# Flight-Mill-Battery.net
KiCad netlist of a schematic drawn in EAGLE
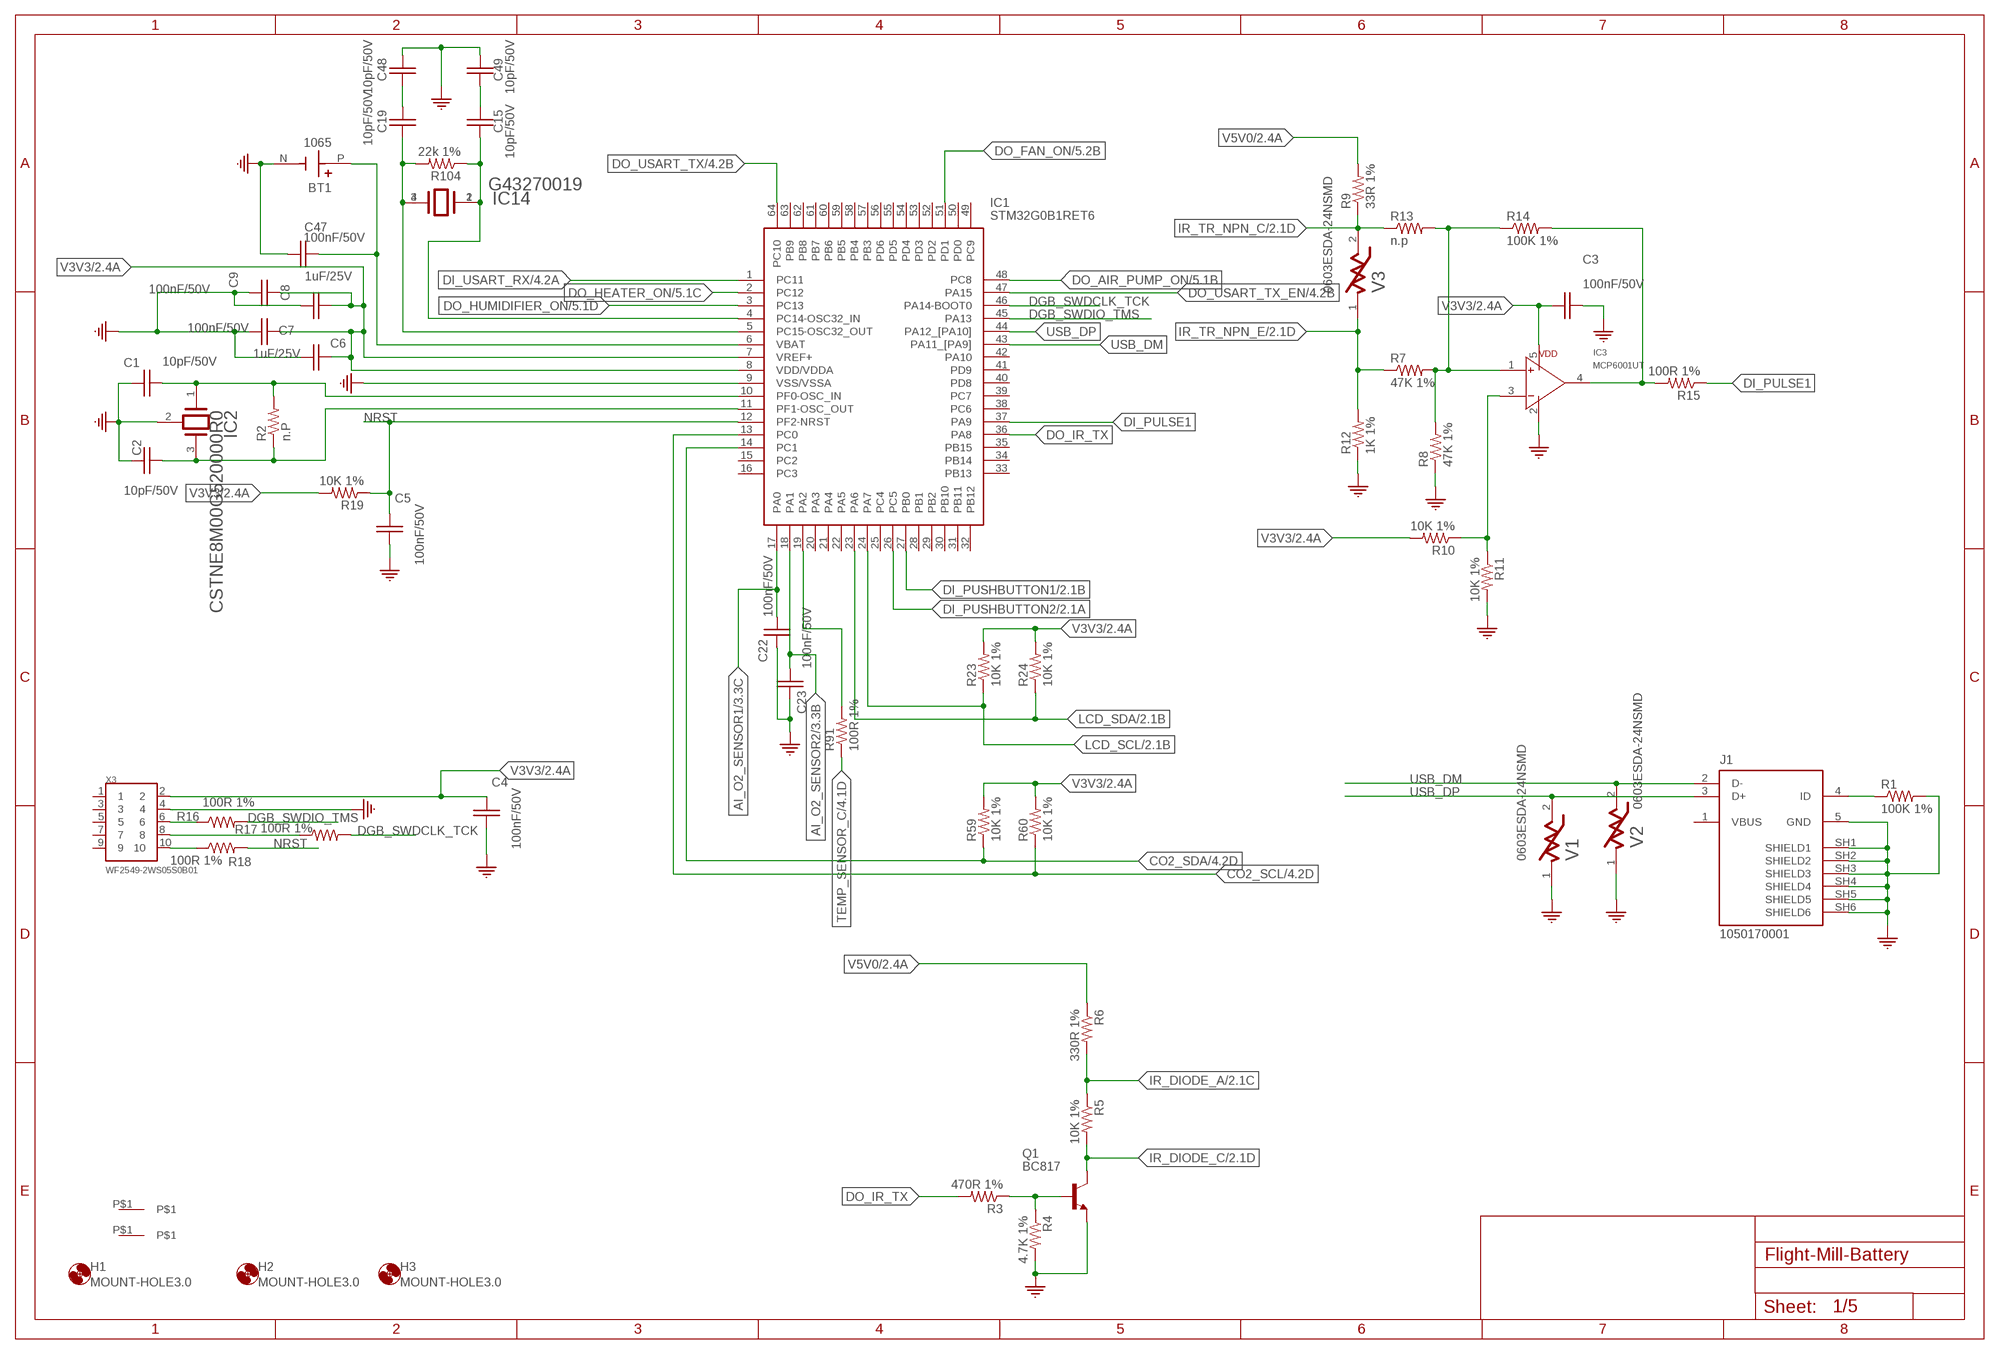
[diagram p0: schematic, sheet 1]
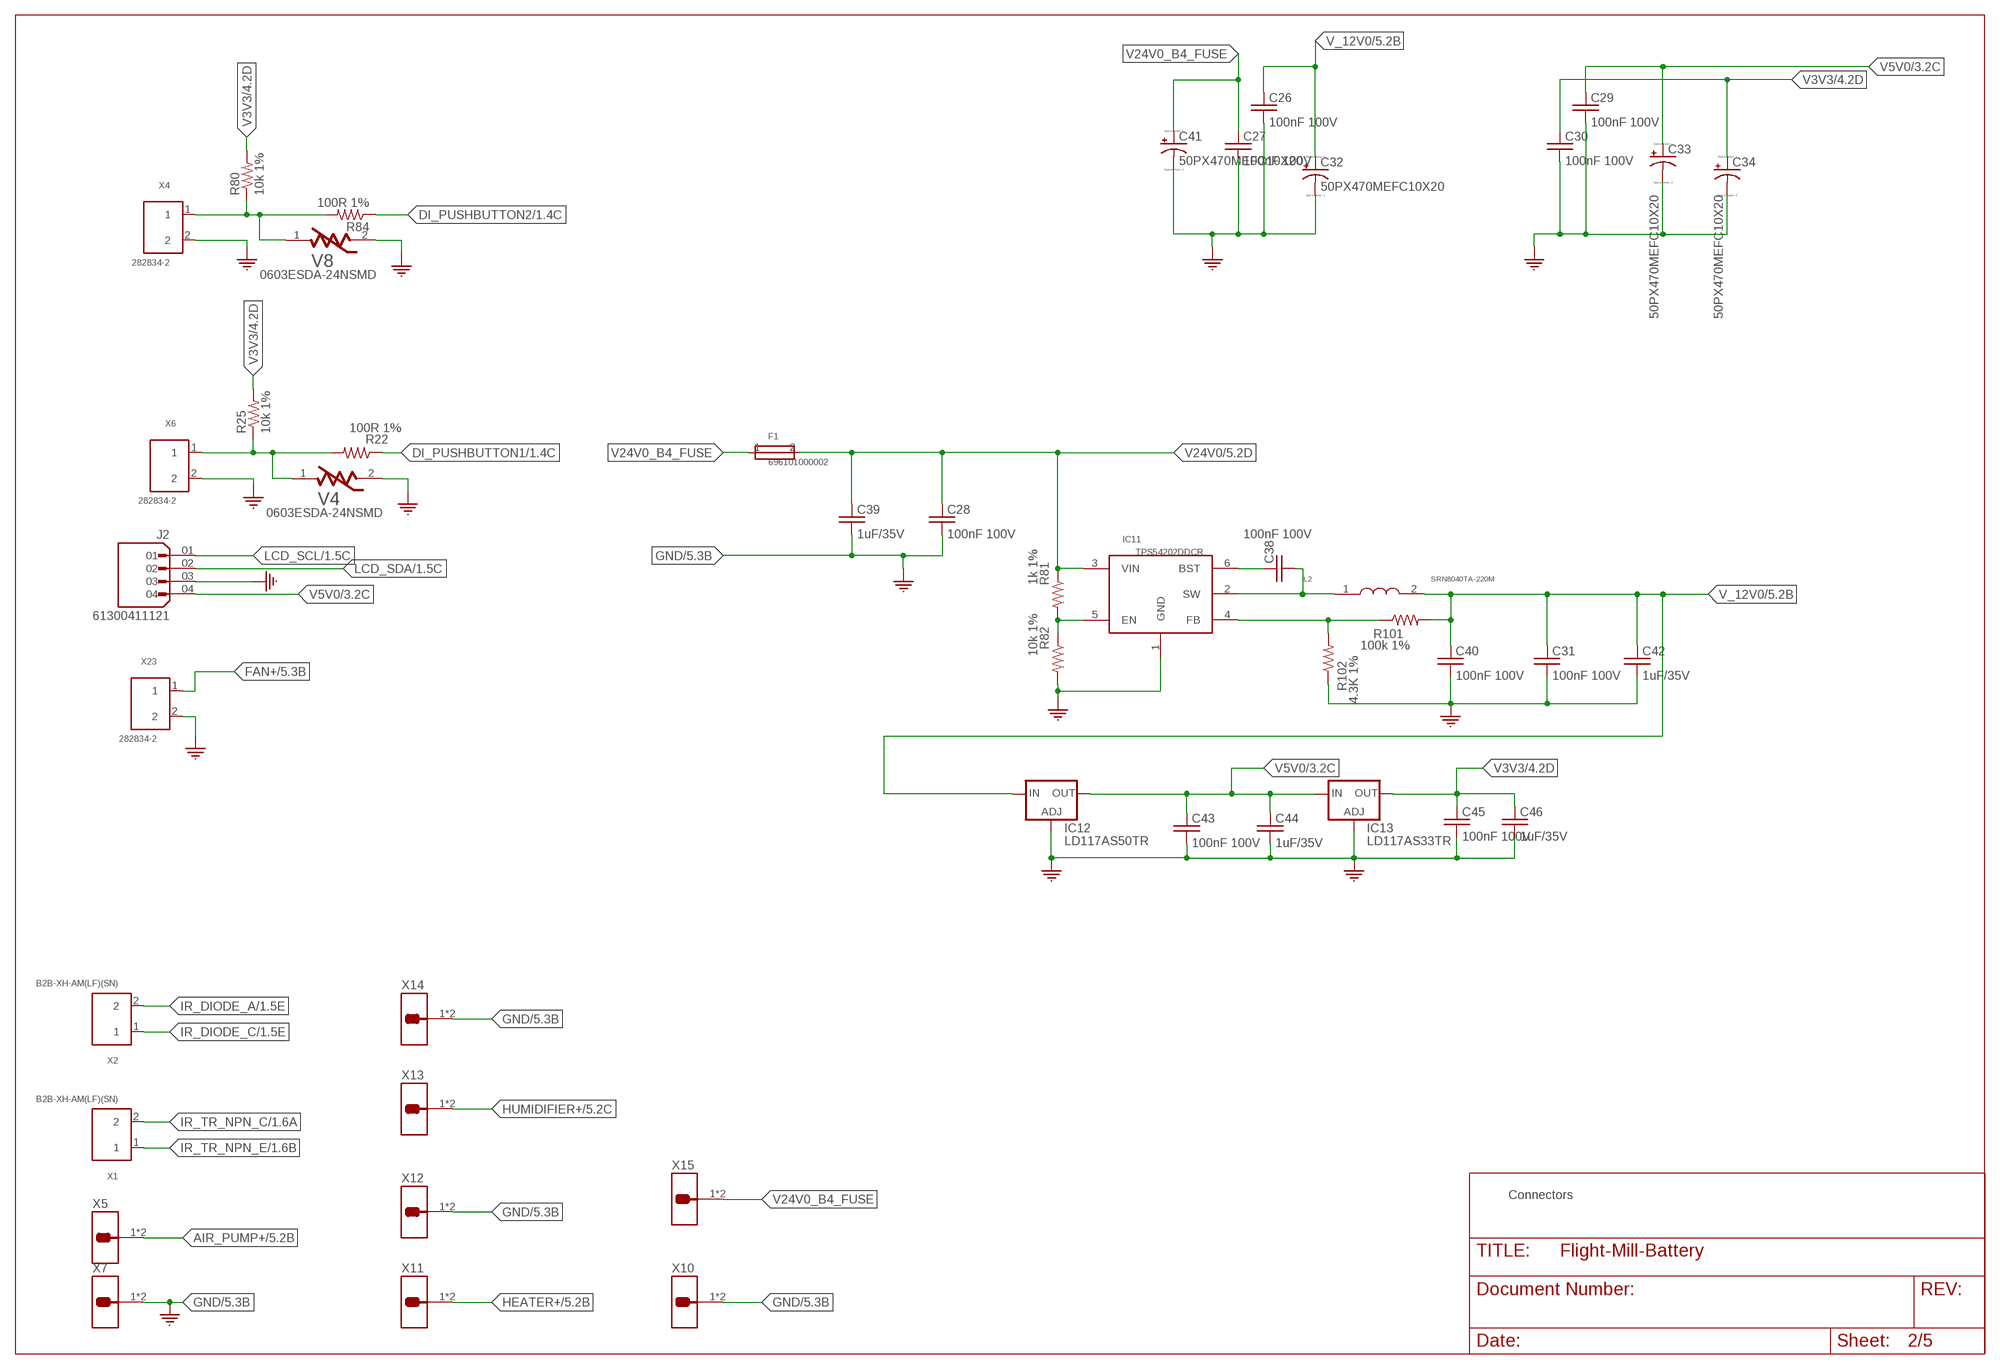
[diagram p1: schematic, sheet 2]
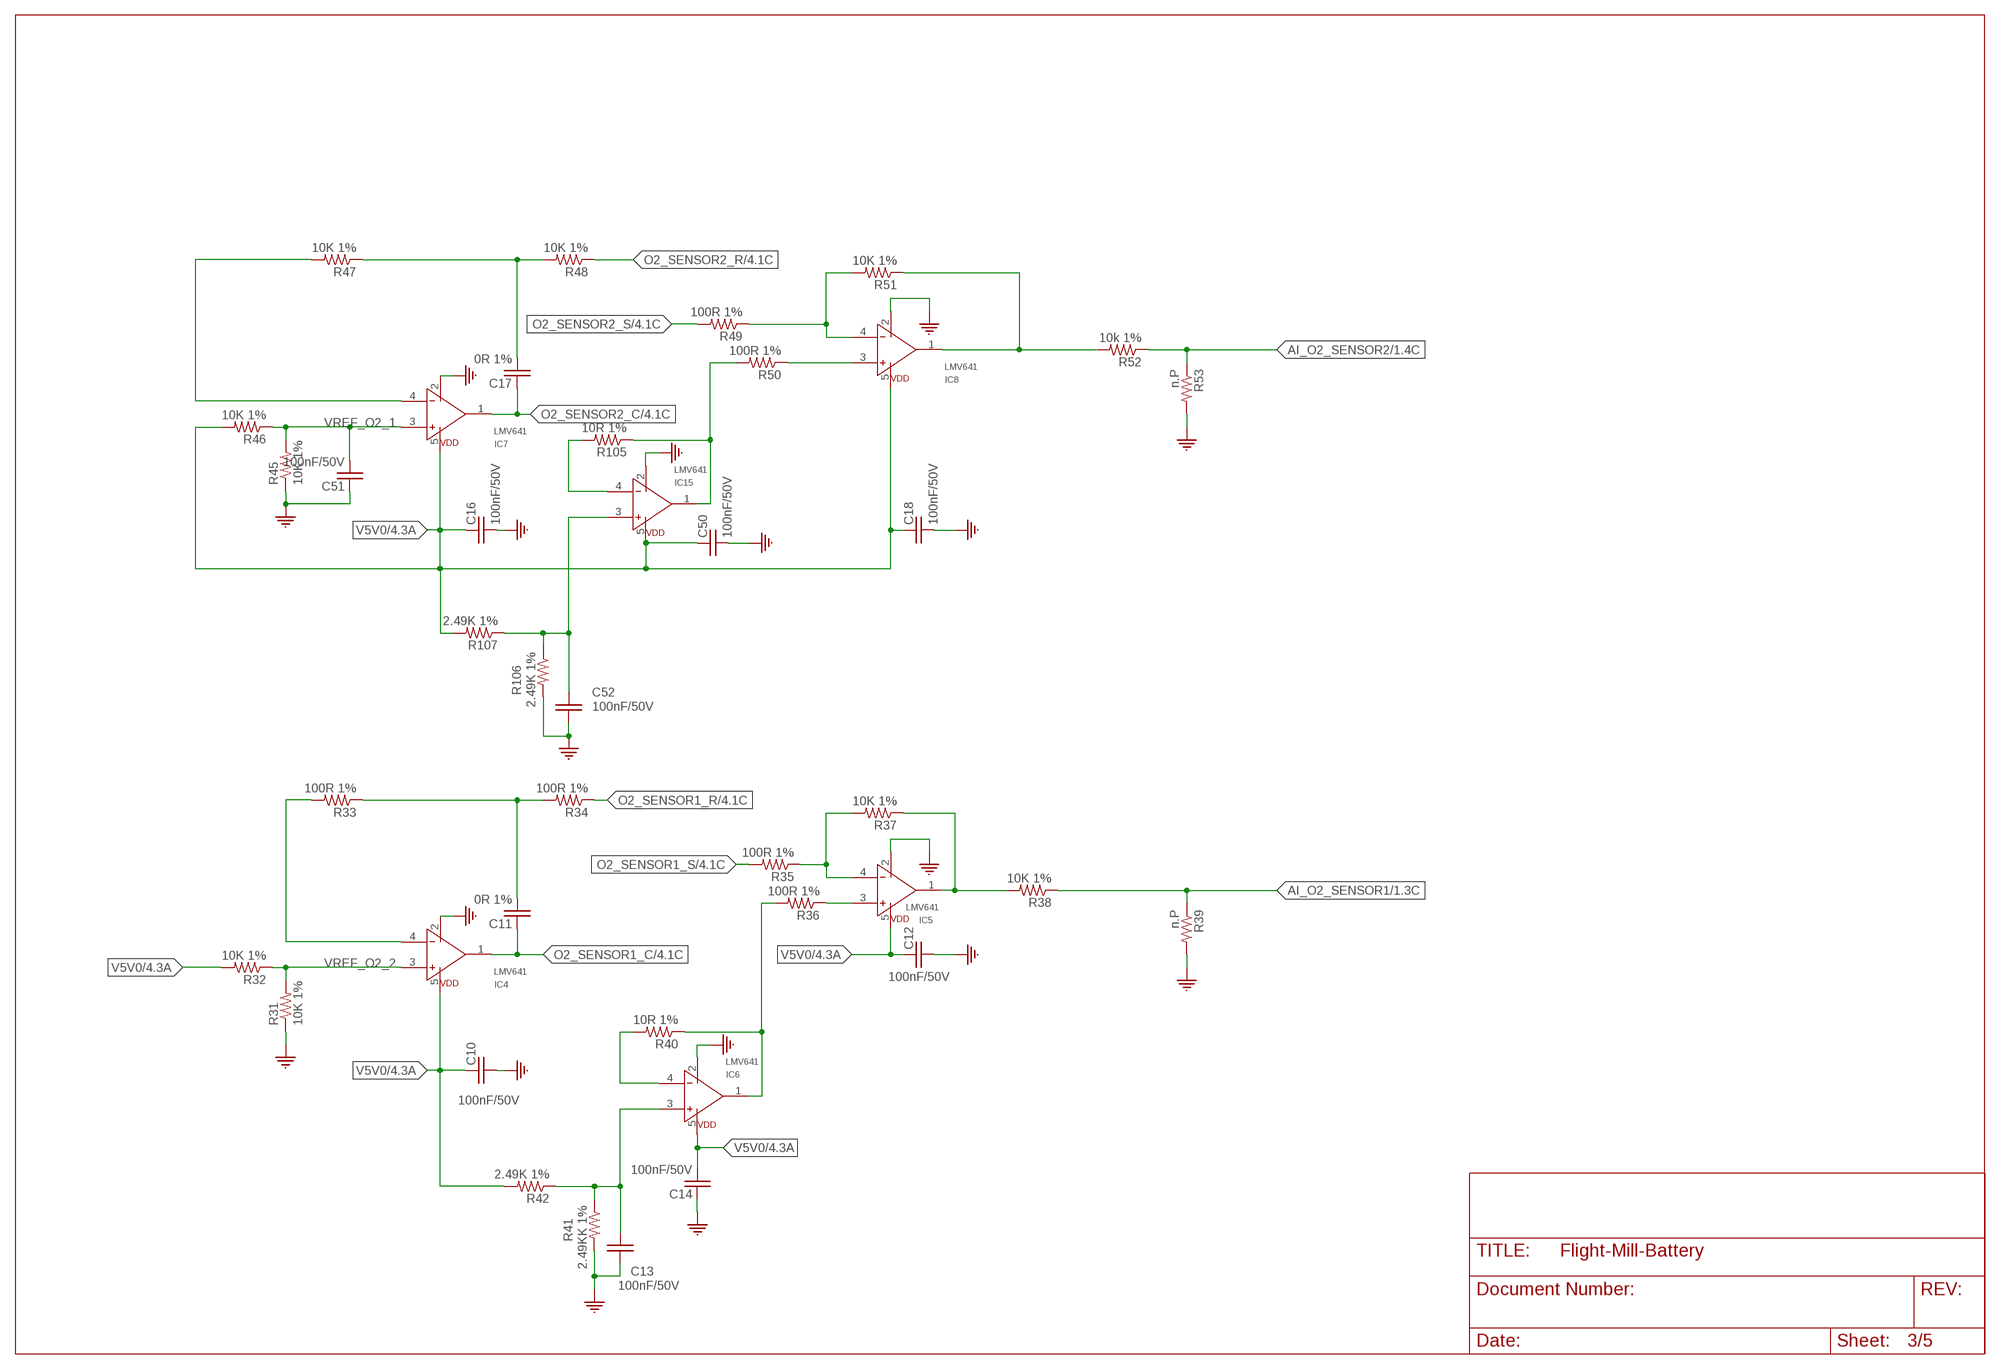
[diagram p2: schematic, sheet 3]
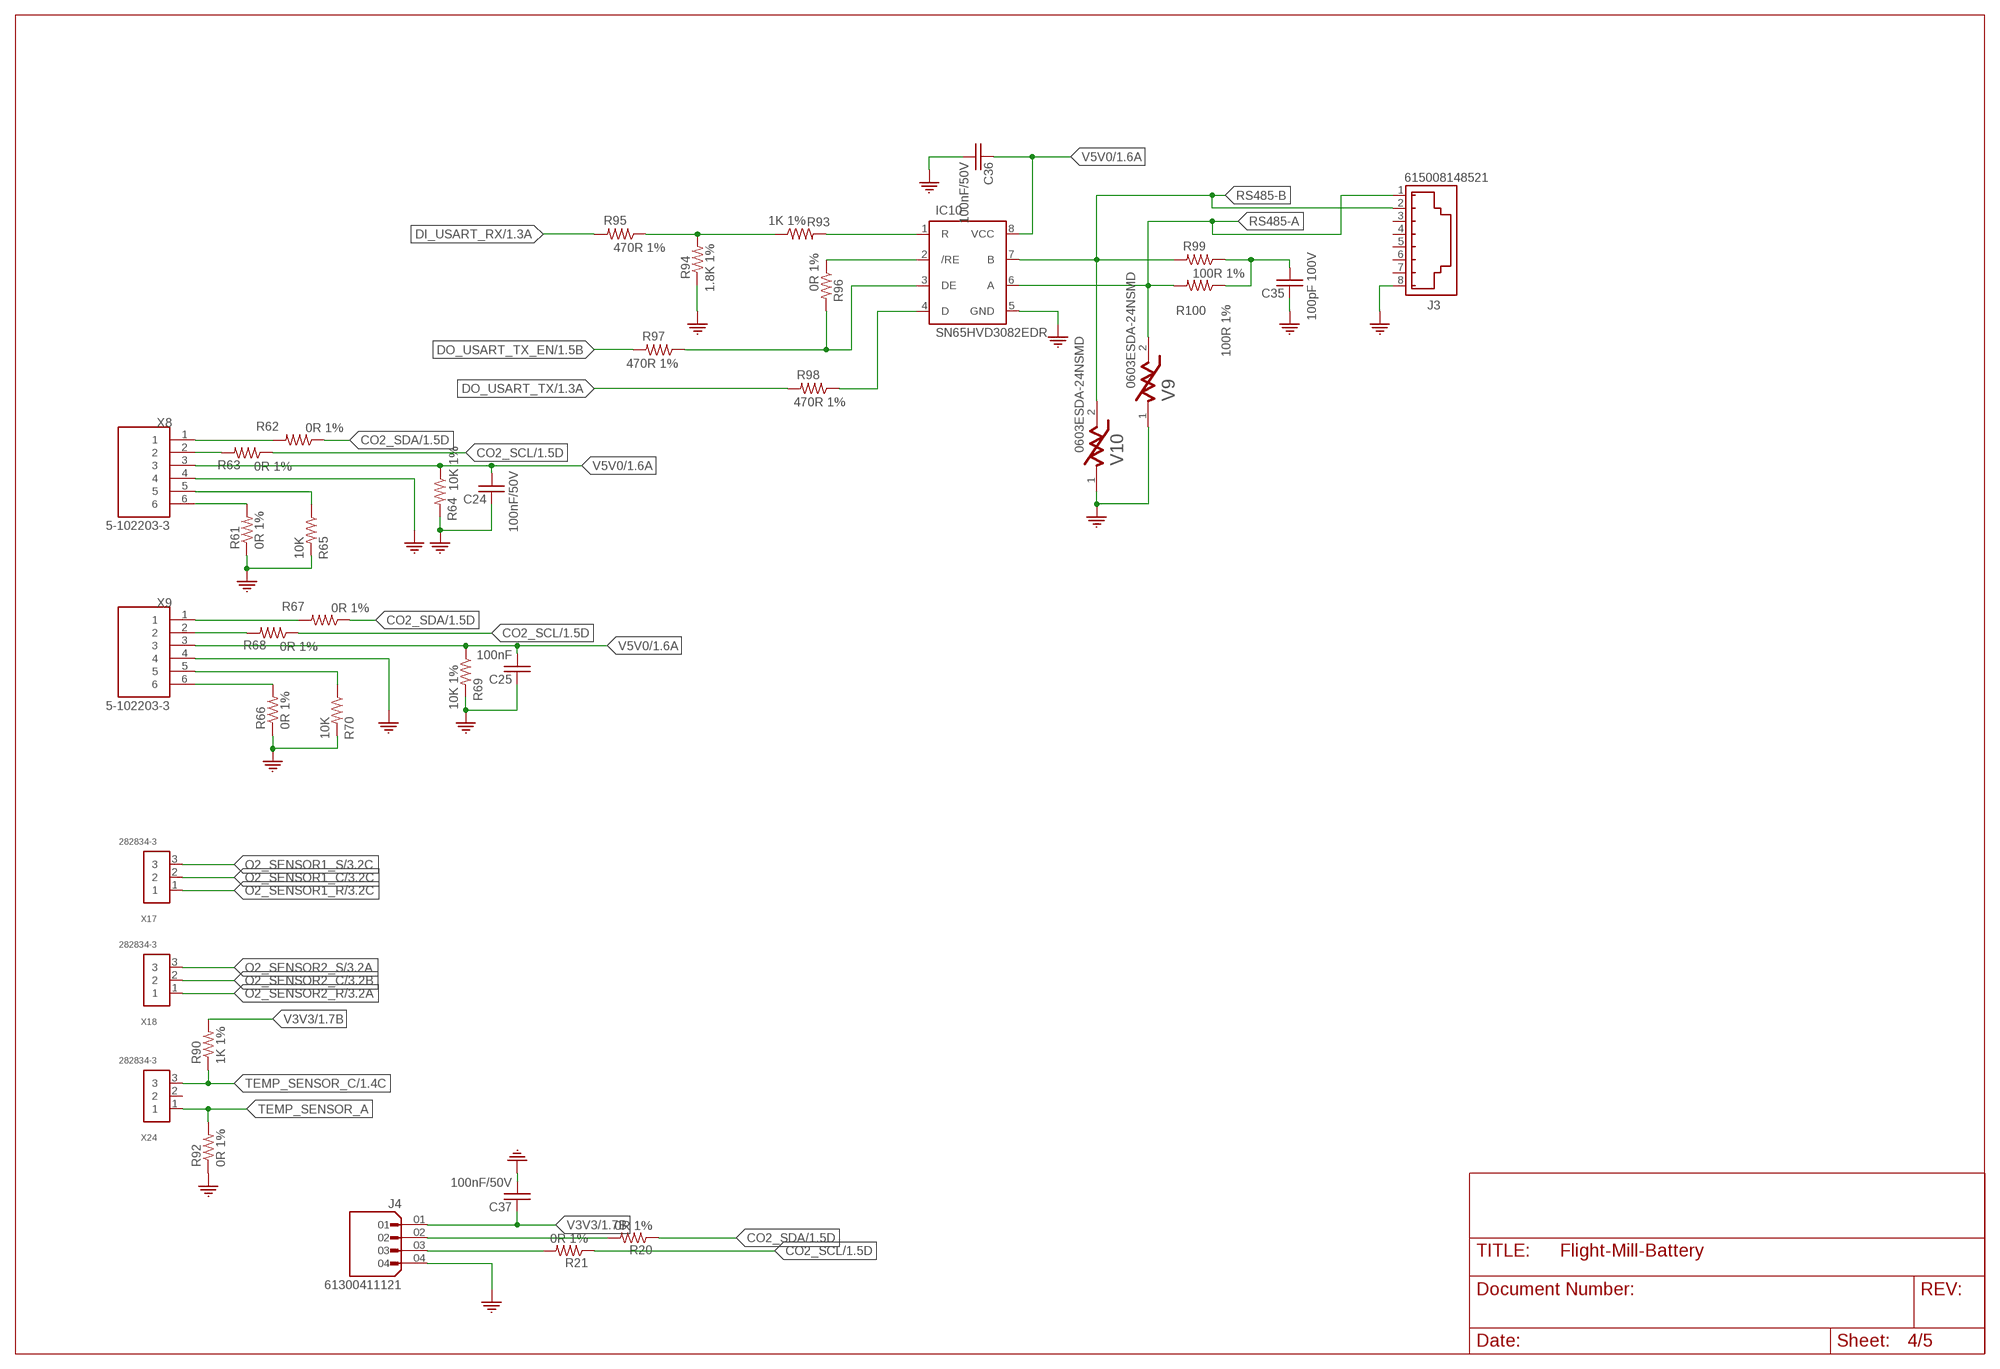
[diagram p3: schematic, sheet 4]
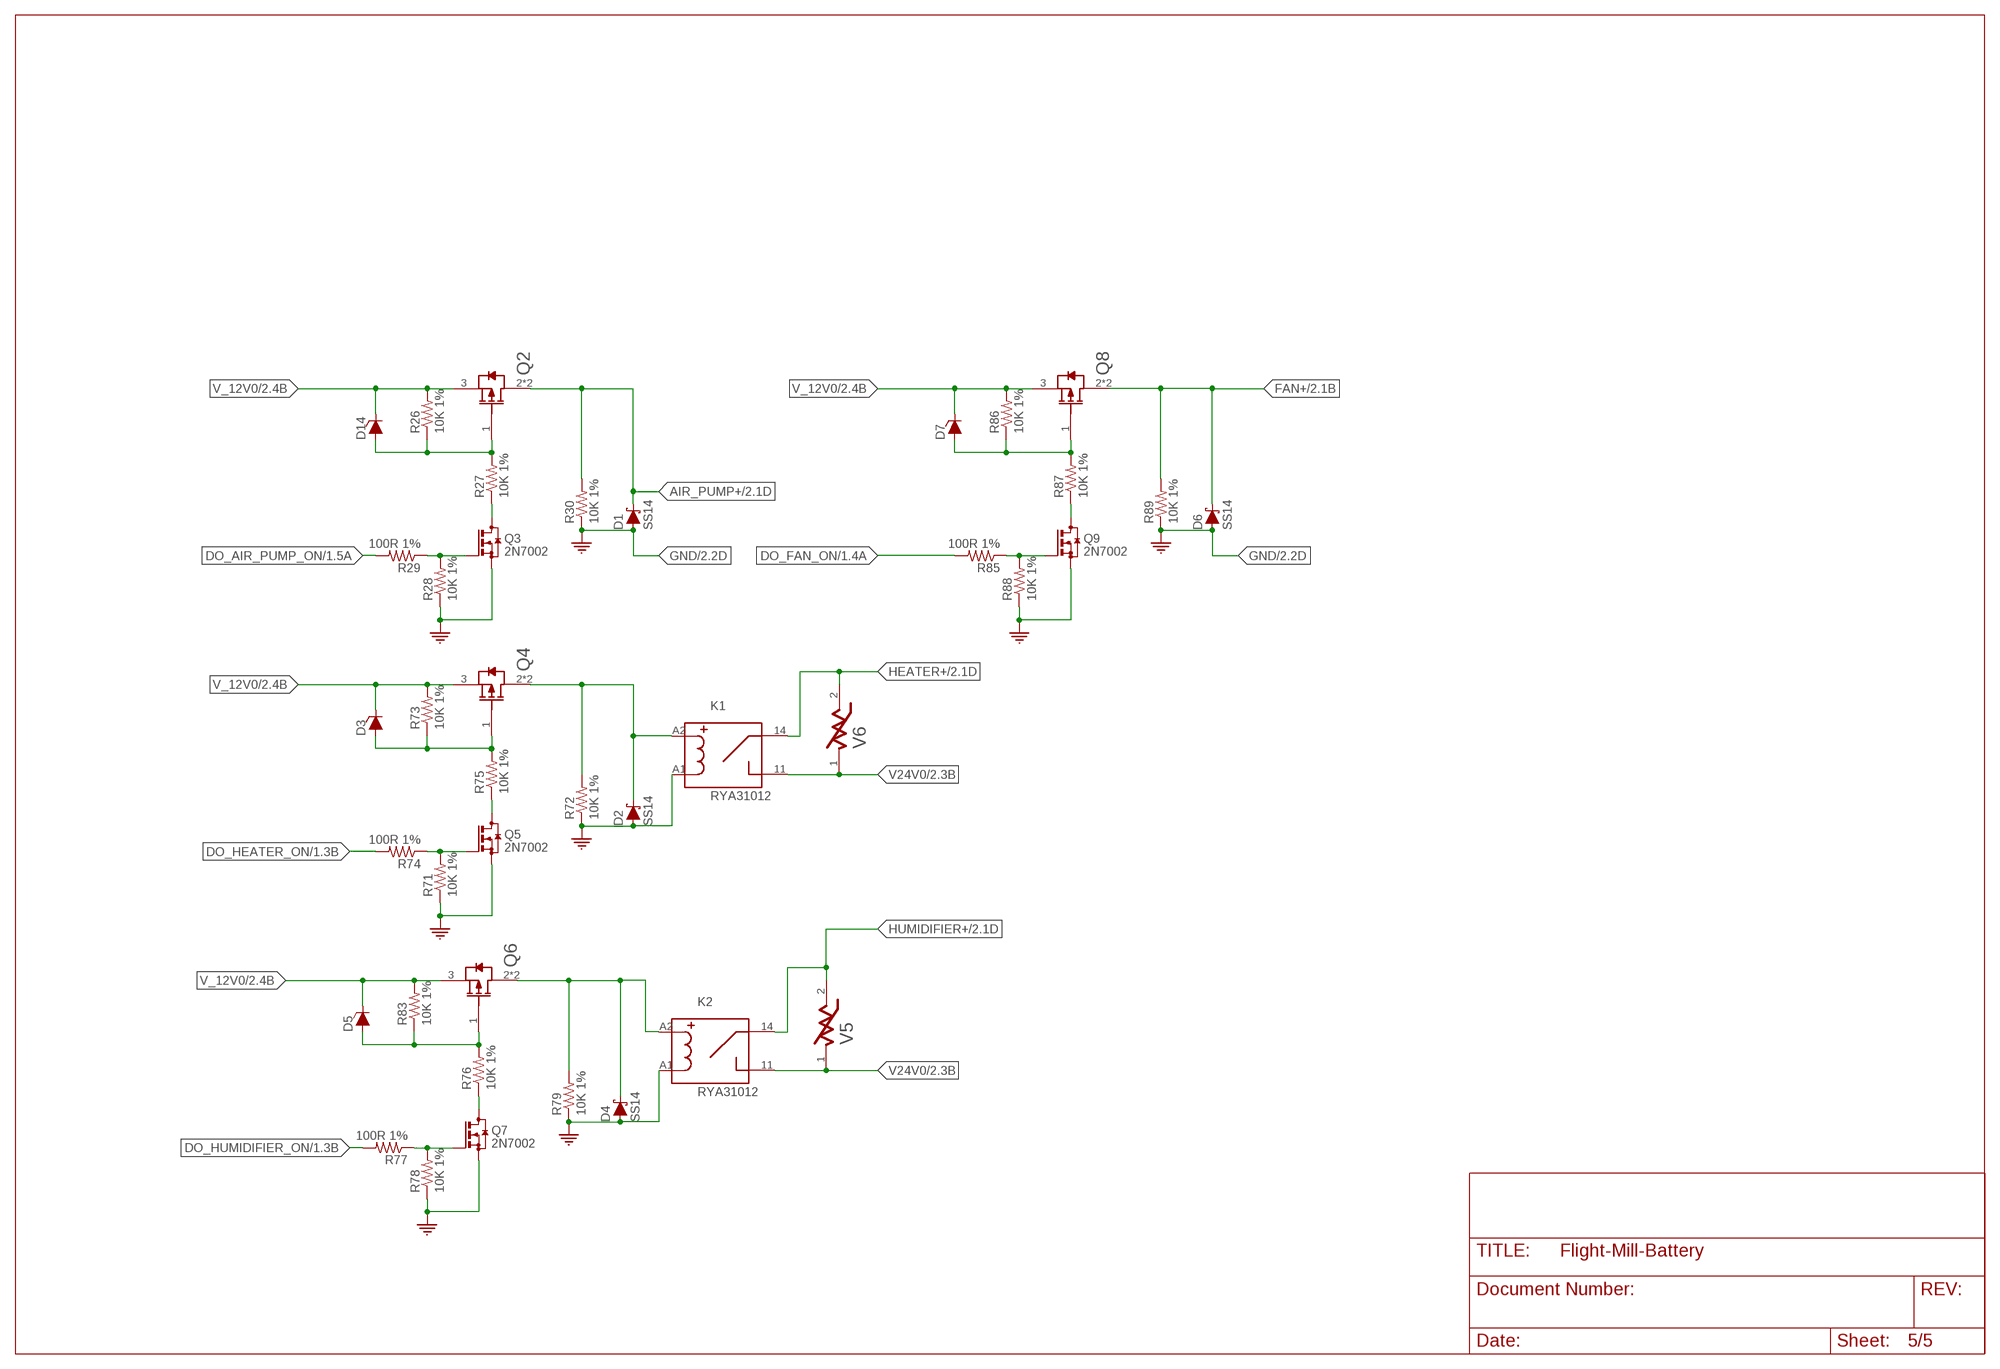
[diagram p4: schematic, sheet 5]

(export (version "E")
  (design (tool "Eeschema 10.0.6"))
  (components
    (comp (ref "C10")
      (value "100nF/50V")
      (footprint "eagle-import:EIA0603")
      (libsource (lib "eagle-import") (part "C_0603EIA0603"))
    )
    (comp (ref "C11")
      (value "0R 1%")
      (footprint "eagle-import:EIA0603")
      (libsource (lib "eagle-import") (part "C_0603EIA0603"))
    )
    (comp (ref "C12")
      (value "100nF/50V")
      (footprint "eagle-import:EIA0603")
      (libsource (lib "eagle-import") (part "C_0603EIA0603"))
    )
    (comp (ref "C13")
      (value "100nF/50V")
      (footprint "eagle-import:EIA0603")
      (libsource (lib "eagle-import") (part "C_0603EIA0603"))
    )
    (comp (ref "C14")
      (value "100nF/50V")
      (footprint "eagle-import:EIA0603")
      (libsource (lib "eagle-import") (part "C_0603EIA0603"))
    )
    (comp (ref "C16")
      (value "100nF/50V")
      (footprint "eagle-import:EIA0603")
      (libsource (lib "eagle-import") (part "C_0603EIA0603"))
    )
    (comp (ref "C17")
      (value "0R 1%")
      (footprint "eagle-import:EIA0603")
      (libsource (lib "eagle-import") (part "C_0603EIA0603"))
    )
    (comp (ref "C18")
      (value "100nF/50V")
      (footprint "eagle-import:EIA0603")
      (libsource (lib "eagle-import") (part "C_0603EIA0603"))
    )
    (comp (ref "C50")
      (value "100nF/50V")
      (footprint "eagle-import:EIA0603")
      (libsource (lib "eagle-import") (part "C_0603EIA0603"))
    )
    (comp (ref "C51")
      (value "100nF/50V")
      (footprint "eagle-import:EIA0603")
      (libsource (lib "eagle-import") (part "C_0603EIA0603"))
    )
    (comp (ref "C52")
      (value "100nF/50V")
      (footprint "eagle-import:EIA0603")
      (libsource (lib "eagle-import") (part "C_0603EIA0603"))
    )
    (comp (ref "IC4")
      (value "LMV641")
      (footprint "eagle-import:SOT-23-5")
      (fields (field (name "MFR") "Texas Instruments"))
      (libsource (lib "eagle-import") (part "LMV641"))
    )
    (comp (ref "IC5")
      (value "LMV641")
      (footprint "eagle-import:SOT-23-5")
      (fields (field (name "MFR") "Texas Instruments"))
      (libsource (lib "eagle-import") (part "LMV641"))
    )
    (comp (ref "IC6")
      (value "LMV641")
      (footprint "eagle-import:SOT-23-5")
      (fields (field (name "MFR") "Texas Instruments"))
      (libsource (lib "eagle-import") (part "LMV641"))
    )
    (comp (ref "IC7")
      (value "LMV641")
      (footprint "eagle-import:SOT-23-5")
      (fields (field (name "MFR") "Texas Instruments"))
      (libsource (lib "eagle-import") (part "LMV641"))
    )
    (comp (ref "IC8")
      (value "LMV641")
      (footprint "eagle-import:SOT-23-5")
      (fields (field (name "MFR") "Texas Instruments"))
      (libsource (lib "eagle-import") (part "LMV641"))
    )
    (comp (ref "IC15")
      (value "LMV641")
      (footprint "eagle-import:SOT-23-5")
      (fields (field (name "MFR") "Texas Instruments"))
      (libsource (lib "eagle-import") (part "LMV641"))
    )
    (comp (ref "R31")
      (value "10K 1%")
      (footprint "eagle-import:EIA0603")
      (libsource (lib "eagle-import") (part "R_0603"))
    )
    (comp (ref "R32")
      (value "10K 1%")
      (footprint "eagle-import:EIA0603")
      (libsource (lib "eagle-import") (part "R_0603"))
    )
    (comp (ref "R33")
      (value "100R 1%")
      (footprint "eagle-import:EIA0603")
      (libsource (lib "eagle-import") (part "R_0603"))
    )
    (comp (ref "R34")
      (value "100R 1%")
      (footprint "eagle-import:EIA0603")
      (libsource (lib "eagle-import") (part "R_0603"))
    )
    (comp (ref "R35")
      (value "100R 1%")
      (footprint "eagle-import:EIA0603")
      (libsource (lib "eagle-import") (part "R_0603"))
    )
    (comp (ref "R36")
      (value "100R 1%")
      (footprint "eagle-import:EIA0603")
      (libsource (lib "eagle-import") (part "R_0603"))
    )
    (comp (ref "R37")
      (value "10K 1%")
      (footprint "eagle-import:EIA0603")
      (libsource (lib "eagle-import") (part "R_0603"))
    )
    (comp (ref "R38")
      (value "10K 1%")
      (footprint "eagle-import:EIA0603")
      (libsource (lib "eagle-import") (part "R_0603"))
    )
    (comp (ref "R39")
      (value "n.P")
      (footprint "eagle-import:EIA0603")
      (libsource (lib "eagle-import") (part "R_0603"))
    )
    (comp (ref "R40")
      (value "10R 1%")
      (footprint "eagle-import:EIA0603")
      (libsource (lib "eagle-import") (part "R_0603"))
    )
    (comp (ref "R41")
      (value "2.49KK 1%")
      (footprint "eagle-import:EIA0603")
      (libsource (lib "eagle-import") (part "R_0603"))
    )
    (comp (ref "R42")
      (value "2.49K 1%")
      (footprint "eagle-import:EIA0603")
      (libsource (lib "eagle-import") (part "R_0603"))
    )
    (comp (ref "R45")
      (value "10K 1%")
      (footprint "eagle-import:EIA0603")
      (libsource (lib "eagle-import") (part "R_0603"))
    )
    (comp (ref "R46")
      (value "10K 1%")
      (footprint "eagle-import:EIA0603")
      (libsource (lib "eagle-import") (part "R_0603"))
    )
    (comp (ref "R47")
      (value "10K 1%")
      (footprint "eagle-import:EIA0603")
      (libsource (lib "eagle-import") (part "R_0603"))
    )
    (comp (ref "R48")
      (value "10K 1%")
      (footprint "eagle-import:EIA0603")
      (libsource (lib "eagle-import") (part "R_0603"))
    )
    (comp (ref "R49")
      (value "100R 1%")
      (footprint "eagle-import:EIA0603")
      (libsource (lib "eagle-import") (part "R_0603"))
    )
    (comp (ref "R50")
      (value "100R 1%")
      (footprint "eagle-import:EIA0603")
      (libsource (lib "eagle-import") (part "R_0603"))
    )
    (comp (ref "R51")
      (value "10K 1%")
      (footprint "eagle-import:EIA0603")
      (libsource (lib "eagle-import") (part "R_0603"))
    )
    (comp (ref "R52")
      (value "10k 1%")
      (footprint "eagle-import:EIA0603")
      (libsource (lib "eagle-import") (part "R_0603"))
    )
    (comp (ref "R53")
      (value "n.P")
      (footprint "eagle-import:EIA0603")
      (libsource (lib "eagle-import") (part "R_0603"))
    )
    (comp (ref "R105")
      (value "10R 1%")
      (footprint "eagle-import:EIA0603")
      (libsource (lib "eagle-import") (part "R_0603"))
    )
    (comp (ref "R106")
      (value "2.49K 1%")
      (footprint "eagle-import:EIA0603")
      (libsource (lib "eagle-import") (part "R_0603"))
    )
    (comp (ref "R107")
      (value "2.49K 1%")
      (footprint "eagle-import:EIA0603")
      (libsource (lib "eagle-import") (part "R_0603"))
    )
    (comp (ref "BT1")
      (value "1065")
      (footprint "eagle-import:BAT_1065")
      (fields (field (name "MF") "Keystone Electronics Corp."))
      (libsource (lib "eagle-import") (part "1065"))
    )
    (comp (ref "C1")
      (value "10pF/50V")
      (footprint "eagle-import:EIA0603")
      (libsource (lib "eagle-import") (part "C_0603EIA0603"))
    )
    (comp (ref "C2")
      (value "10pF/50V")
      (footprint "eagle-import:EIA0603")
      (libsource (lib "eagle-import") (part "C_0603EIA0603"))
    )
    (comp (ref "C3")
      (value "100nF/50V")
      (footprint "eagle-import:EIA0603")
      (libsource (lib "eagle-import") (part "C_0603EIA0603"))
    )
    (comp (ref "C4")
      (value "100nF/50V")
      (footprint "eagle-import:EIA0603")
      (libsource (lib "eagle-import") (part "C_0603EIA0603"))
    )
    (comp (ref "C5")
      (value "100nF/50V")
      (footprint "eagle-import:EIA0603")
      (libsource (lib "eagle-import") (part "C_0603EIA0603"))
    )
    (comp (ref "C6")
      (value "1uF/25V")
      (footprint "eagle-import:EIA0603")
      (libsource (lib "eagle-import") (part "C_0603EIA0603"))
    )
    (comp (ref "C7")
      (value "100nF/50V")
      (footprint "eagle-import:EIA0603")
      (libsource (lib "eagle-import") (part "C_0603EIA0603"))
    )
    (comp (ref "C8")
      (value "1uF/25V")
      (footprint "eagle-import:EIA0603")
      (libsource (lib "eagle-import") (part "C_0603EIA0603"))
    )
    (comp (ref "C9")
      (value "100nF/50V")
      (footprint "eagle-import:EIA0603")
      (libsource (lib "eagle-import") (part "C_0603EIA0603"))
    )
    (comp (ref "C15")
      (value "10pF/50V")
      (footprint "eagle-import:EIA0603")
      (libsource (lib "eagle-import") (part "C_0603EIA0603"))
    )
    (comp (ref "C19")
      (value "10pF/50V")
      (footprint "eagle-import:EIA0603")
      (libsource (lib "eagle-import") (part "C_0603EIA0603"))
    )
    (comp (ref "C22")
      (value "100nF/50V")
      (footprint "eagle-import:EIA0603")
      (libsource (lib "eagle-import") (part "C_0603EIA0603"))
    )
    (comp (ref "C23")
      (value "100nF/50V")
      (footprint "eagle-import:EIA0603")
      (libsource (lib "eagle-import") (part "C_0603EIA0603"))
    )
    (comp (ref "C47")
      (value "100nF/50V")
      (footprint "eagle-import:EIA0603")
      (libsource (lib "eagle-import") (part "C_0603EIA0603"))
    )
    (comp (ref "C48")
      (value "10pF/50V")
      (footprint "eagle-import:EIA0603")
      (libsource (lib "eagle-import") (part "C_0603EIA0603"))
    )
    (comp (ref "C49")
      (value "10pF/50V")
      (footprint "eagle-import:EIA0603")
      (libsource (lib "eagle-import") (part "C_0603EIA0603"))
    )
    (comp (ref "FID1")
      (value "FIDUCIAL")
      (footprint "eagle-import:FIDUCIAL")
      (libsource (lib "eagle-import") (part "FIDUCIAL"))
    )
    (comp (ref "FID2")
      (value "FIDUCIAL")
      (footprint "eagle-import:FIDUCIAL")
      (libsource (lib "eagle-import") (part "FIDUCIAL"))
    )
    (comp (ref "H1")
      (value "MOUNT-HOLE3.0")
      (footprint "eagle-import:3,0")
      (libsource (lib "eagle-import") (part "MOUNT-HOLE3.0"))
    )
    (comp (ref "H2")
      (value "MOUNT-HOLE3.0")
      (footprint "eagle-import:3,0")
      (libsource (lib "eagle-import") (part "MOUNT-HOLE3.0"))
    )
    (comp (ref "H3")
      (value "MOUNT-HOLE3.0")
      (footprint "eagle-import:3,0")
      (libsource (lib "eagle-import") (part "MOUNT-HOLE3.0"))
    )
    (comp (ref "IC1")
      (value "STM32G0B1RET6")
      (footprint "eagle-import:QFP50P1200X1200X160-64N")
      (fields (field (name "MOUSER_PART_NUMBER") "511-STM32G0B1RET6"))
      (libsource (lib "eagle-import") (part "STM32G0B1RET6"))
    )
    (comp (ref "IC2")
      (value "CSTNE8M00G520000R0")
      (footprint "eagle-import:CSTNE8M00G520000R0")
      (fields (field (name "MFR") "Murata"))
      (libsource (lib "eagle-import") (part "CSTNE8M00G520000R0"))
    )
    (comp (ref "IC3")
      (value "MCP6001UT")
      (footprint "eagle-import:SOT-23-5")
      (libsource (lib "eagle-import") (part "MCP6001UT"))
    )
    (comp (ref "IC14")
      (value "G43270019")
      (footprint "eagle-import:G43270019")
      (fields (field (name "MFR") "Diodes Inc"))
      (libsource (lib "eagle-import") (part "G43270019"))
    )
    (comp (ref "J1")
      (value "1050170001")
      (footprint "eagle-import:MOLEX_1050170001")
      (fields (field (name "MF") "Molex"))
      (libsource (lib "eagle-import") (part "1050170001"))
    )
    (comp (ref "Q1")
      (value "BC817")
      (footprint "eagle-import:SOT23")
      (fields (field (name "MFR") "NXP"))
      (libsource (lib "eagle-import") (part "BC817"))
    )
    (comp (ref "R1")
      (value "100K 1%")
      (footprint "eagle-import:EIA0603")
      (libsource (lib "eagle-import") (part "R_0603"))
    )
    (comp (ref "R2")
      (value "n.P")
      (footprint "eagle-import:EIA0603")
      (libsource (lib "eagle-import") (part "R_0603"))
    )
    (comp (ref "R3")
      (value "470R 1%")
      (footprint "eagle-import:EIA0603")
      (libsource (lib "eagle-import") (part "R_0603"))
    )
    (comp (ref "R4")
      (value "4.7K 1%")
      (footprint "eagle-import:EIA0603")
      (libsource (lib "eagle-import") (part "R_0603"))
    )
    (comp (ref "R5")
      (value "10K 1%")
      (footprint "eagle-import:EIA0603")
      (libsource (lib "eagle-import") (part "R_0603"))
    )
    (comp (ref "R6")
      (value "330R 1%")
      (footprint "eagle-import:EIA0603")
      (libsource (lib "eagle-import") (part "R_0603"))
    )
    (comp (ref "R7")
      (value "47K 1%")
      (footprint "eagle-import:EIA0603")
      (libsource (lib "eagle-import") (part "R_0603"))
    )
    (comp (ref "R8")
      (value "47K 1%")
      (footprint "eagle-import:EIA0603")
      (libsource (lib "eagle-import") (part "R_0603"))
    )
    (comp (ref "R9")
      (value "33R 1%")
      (footprint "eagle-import:EIA0603")
      (libsource (lib "eagle-import") (part "R_0603"))
    )
    (comp (ref "R10")
      (value "10K 1%")
      (footprint "eagle-import:EIA0603")
      (libsource (lib "eagle-import") (part "R_0603"))
    )
    (comp (ref "R11")
      (value "10K 1%")
      (footprint "eagle-import:EIA0603")
      (libsource (lib "eagle-import") (part "R_0603"))
    )
    (comp (ref "R12")
      (value "1K 1%")
      (footprint "eagle-import:EIA0603")
      (libsource (lib "eagle-import") (part "R_0603"))
    )
    (comp (ref "R13")
      (value "n.p")
      (footprint "eagle-import:EIA0603")
      (libsource (lib "eagle-import") (part "R_0603"))
    )
    (comp (ref "R14")
      (value "100K 1%")
      (footprint "eagle-import:EIA0603")
      (libsource (lib "eagle-import") (part "R_0603"))
    )
    (comp (ref "R15")
      (value "100R 1%")
      (footprint "eagle-import:EIA0603")
      (libsource (lib "eagle-import") (part "R_0603"))
    )
    (comp (ref "R16")
      (value "100R 1%")
      (footprint "eagle-import:EIA0603")
      (libsource (lib "eagle-import") (part "R_0603"))
    )
    (comp (ref "R17")
      (value "100R 1%")
      (footprint "eagle-import:EIA0603")
      (libsource (lib "eagle-import") (part "R_0603"))
    )
    (comp (ref "R18")
      (value "100R 1%")
      (footprint "eagle-import:EIA0603")
      (libsource (lib "eagle-import") (part "R_0603"))
    )
    (comp (ref "R19")
      (value "10K 1%")
      (footprint "eagle-import:EIA0603")
      (libsource (lib "eagle-import") (part "R_0603"))
    )
    (comp (ref "R23")
      (value "10K 1%")
      (footprint "eagle-import:EIA0603")
      (libsource (lib "eagle-import") (part "R_0603"))
    )
    (comp (ref "R24")
      (value "10K 1%")
      (footprint "eagle-import:EIA0603")
      (libsource (lib "eagle-import") (part "R_0603"))
    )
    (comp (ref "R59")
      (value "10K 1%")
      (footprint "eagle-import:EIA0603")
      (libsource (lib "eagle-import") (part "R_0603"))
    )
    (comp (ref "R60")
      (value "10K 1%")
      (footprint "eagle-import:EIA0603")
      (libsource (lib "eagle-import") (part "R_0603"))
    )
    (comp (ref "R91")
      (value "100R 1%")
      (footprint "eagle-import:EIA0603")
      (libsource (lib "eagle-import") (part "R_0603"))
    )
    (comp (ref "R104")
      (value "22k 1%")
      (footprint "eagle-import:EIA0603")
      (libsource (lib "eagle-import") (part "R_0603"))
    )
    (comp (ref "V1")
      (value "0603ESDA-24NSMD")
      (footprint "eagle-import:EIA0603")
      (fields (field (name "MFR") "Bourns"))
      (libsource (lib "eagle-import") (part "0603ESDA-24NSMD"))
    )
    (comp (ref "V2")
      (value "0603ESDA-24NSMD")
      (footprint "eagle-import:EIA0603")
      (fields (field (name "MFR") "Bourns"))
      (libsource (lib "eagle-import") (part "0603ESDA-24NSMD"))
    )
    (comp (ref "V3")
      (value "0603ESDA-24NSMD")
      (footprint "eagle-import:EIA0603")
      (fields (field (name "MFR") "Bourns"))
      (libsource (lib "eagle-import") (part "0603ESDA-24NSMD"))
    )
    (comp (ref "X3")
      (value "WF2549-2WS05S0B01")
      (footprint "eagle-import:X10_100MIL_2XROW_VERT")
      (fields (field (name "MFR") "WCON"))
      (libsource (lib "eagle-import") (part "WF2549-2WS05S0B01"))
    )
    (comp (ref "D1")
      (value "SS14")
      (footprint "eagle-import:SMA")
      (fields (field (name "MFR") "MCC"))
      (libsource (lib "eagle-import") (part "SS14"))
    )
    (comp (ref "D2")
      (value "SS14")
      (footprint "eagle-import:SMA")
      (fields (field (name "MFR") "MCC"))
      (libsource (lib "eagle-import") (part "SS14"))
    )
    (comp (ref "D3")
      (value "MMBZ4696-HE3-18")
      (footprint "eagle-import:SOT23-3")
      (fields (field (name "MFR") "Vishay"))
      (libsource (lib "eagle-import") (part "MMBZ4696-HE3-18"))
    )
    (comp (ref "D4")
      (value "SS14")
      (footprint "eagle-import:SMA")
      (fields (field (name "MFR") "MCC"))
      (libsource (lib "eagle-import") (part "SS14"))
    )
    (comp (ref "D5")
      (value "MMBZ4696-HE3-18")
      (footprint "eagle-import:SOT23-3")
      (fields (field (name "MFR") "Vishay"))
      (libsource (lib "eagle-import") (part "MMBZ4696-HE3-18"))
    )
    (comp (ref "D6")
      (value "SS14")
      (footprint "eagle-import:SMA")
      (fields (field (name "MFR") "MCC"))
      (libsource (lib "eagle-import") (part "SS14"))
    )
    (comp (ref "D7")
      (value "MMBZ4696-HE3-18")
      (footprint "eagle-import:SOT23-3")
      (fields (field (name "MFR") "Vishay"))
      (libsource (lib "eagle-import") (part "MMBZ4696-HE3-18"))
    )
    (comp (ref "D14")
      (value "MMBZ4696-HE3-18")
      (footprint "eagle-import:SOT23-3")
      (fields (field (name "MFR") "Vishay"))
      (libsource (lib "eagle-import") (part "MMBZ4696-HE3-18"))
    )
    (comp (ref "K1")
      (value "RYA31012")
      (footprint "eagle-import:RYA31012")
      (fields (field (name "MFR") "TE Connectivity"))
      (libsource (lib "eagle-import") (part "RYA31012"))
    )
    (comp (ref "K2")
      (value "RYA31012")
      (footprint "eagle-import:RYA31012")
      (fields (field (name "MFR") "TE Connectivity"))
      (libsource (lib "eagle-import") (part "RYA31012"))
    )
    (comp (ref "Q2")
      (value "UT2955G-AA3-R")
      (footprint "eagle-import:SOT223")
      (fields (field (name "MFR") "UTC"))
      (libsource (lib "eagle-import") (part "UT2955G-AA3-R"))
    )
    (comp (ref "Q3")
      (value "2N7002")
      (footprint "eagle-import:SOT23")
      (fields (field (name "MFR") "Diodes, Guangdong Hotetech,NXP"))
      (libsource (lib "eagle-import") (part "2N7002"))
    )
    (comp (ref "Q4")
      (value "UT2955G-AA3-R")
      (footprint "eagle-import:SOT223")
      (fields (field (name "MFR") "UTC"))
      (libsource (lib "eagle-import") (part "UT2955G-AA3-R"))
    )
    (comp (ref "Q5")
      (value "2N7002")
      (footprint "eagle-import:SOT23")
      (fields (field (name "MFR") "Diodes, Guangdong Hotetech,NXP"))
      (libsource (lib "eagle-import") (part "2N7002"))
    )
    (comp (ref "Q6")
      (value "UT2955G-AA3-R")
      (footprint "eagle-import:SOT223")
      (fields (field (name "MFR") "UTC"))
      (libsource (lib "eagle-import") (part "UT2955G-AA3-R"))
    )
    (comp (ref "Q7")
      (value "2N7002")
      (footprint "eagle-import:SOT23")
      (fields (field (name "MFR") "Diodes, Guangdong Hotetech,NXP"))
      (libsource (lib "eagle-import") (part "2N7002"))
    )
    (comp (ref "Q8")
      (value "UT2955G-AA3-R")
      (footprint "eagle-import:SOT223")
      (fields (field (name "MFR") "UTC"))
      (libsource (lib "eagle-import") (part "UT2955G-AA3-R"))
    )
    (comp (ref "Q9")
      (value "2N7002")
      (footprint "eagle-import:SOT23")
      (fields (field (name "MFR") "Diodes, Guangdong Hotetech,NXP"))
      (libsource (lib "eagle-import") (part "2N7002"))
    )
    (comp (ref "R26")
      (value "10K 1%")
      (footprint "eagle-import:EIA0603")
      (libsource (lib "eagle-import") (part "R_0603"))
    )
    (comp (ref "R27")
      (value "10K 1%")
      (footprint "eagle-import:EIA0603")
      (libsource (lib "eagle-import") (part "R_0603"))
    )
    (comp (ref "R28")
      (value "10K 1%")
      (footprint "eagle-import:EIA0603")
      (libsource (lib "eagle-import") (part "R_0603"))
    )
    (comp (ref "R29")
      (value "100R 1%")
      (footprint "eagle-import:EIA0603")
      (libsource (lib "eagle-import") (part "R_0603"))
    )
    (comp (ref "R30")
      (value "10K 1%")
      (footprint "eagle-import:EIA0603")
      (libsource (lib "eagle-import") (part "R_0603"))
    )
    (comp (ref "R71")
      (value "10K 1%")
      (footprint "eagle-import:EIA0603")
      (libsource (lib "eagle-import") (part "R_0603"))
    )
    (comp (ref "R72")
      (value "10K 1%")
      (footprint "eagle-import:EIA0603")
      (libsource (lib "eagle-import") (part "R_0603"))
    )
    (comp (ref "R73")
      (value "10K 1%")
      (footprint "eagle-import:EIA0603")
      (libsource (lib "eagle-import") (part "R_0603"))
    )
    (comp (ref "R74")
      (value "100R 1%")
      (footprint "eagle-import:EIA0603")
      (libsource (lib "eagle-import") (part "R_0603"))
    )
    (comp (ref "R75")
      (value "10K 1%")
      (footprint "eagle-import:EIA0603")
      (libsource (lib "eagle-import") (part "R_0603"))
    )
    (comp (ref "R76")
      (value "10K 1%")
      (footprint "eagle-import:EIA0603")
      (libsource (lib "eagle-import") (part "R_0603"))
    )
    (comp (ref "R77")
      (value "100R 1%")
      (footprint "eagle-import:EIA0603")
      (libsource (lib "eagle-import") (part "R_0603"))
    )
    (comp (ref "R78")
      (value "10K 1%")
      (footprint "eagle-import:EIA0603")
      (libsource (lib "eagle-import") (part "R_0603"))
    )
    (comp (ref "R79")
      (value "10K 1%")
      (footprint "eagle-import:EIA0603")
      (libsource (lib "eagle-import") (part "R_0603"))
    )
    (comp (ref "R83")
      (value "10K 1%")
      (footprint "eagle-import:EIA0603")
      (libsource (lib "eagle-import") (part "R_0603"))
    )
    (comp (ref "R85")
      (value "100R 1%")
      (footprint "eagle-import:EIA0603")
      (libsource (lib "eagle-import") (part "R_0603"))
    )
    (comp (ref "R86")
      (value "10K 1%")
      (footprint "eagle-import:EIA0603")
      (libsource (lib "eagle-import") (part "R_0603"))
    )
    (comp (ref "R87")
      (value "10K 1%")
      (footprint "eagle-import:EIA0603")
      (libsource (lib "eagle-import") (part "R_0603"))
    )
    (comp (ref "R88")
      (value "10K 1%")
      (footprint "eagle-import:EIA0603")
      (libsource (lib "eagle-import") (part "R_0603"))
    )
    (comp (ref "R89")
      (value "10K 1%")
      (footprint "eagle-import:EIA0603")
      (libsource (lib "eagle-import") (part "R_0603"))
    )
    (comp (ref "V5")
      (value "B72205S0271K101B72205S2131K101")
      (footprint "eagle-import:EPCOS_B72205S0271K101_0")
      (fields (field (name "MFR") "EPCOS"))
      (libsource (lib "eagle-import") (part "B72205S0271K101B72205S2131K101"))
    )
    (comp (ref "V6")
      (value "B72205S0271K101B72205S2131K101")
      (footprint "eagle-import:EPCOS_B72205S0271K101_0")
      (fields (field (name "MFR") "EPCOS"))
      (libsource (lib "eagle-import") (part "B72205S0271K101B72205S2131K101"))
    )
    (comp (ref "C26")
      (value "100nF 100V")
      (footprint "eagle-import:EIA0603")
      (libsource (lib "eagle-import") (part "C_0603EIA0603"))
    )
    (comp (ref "C27")
      (value "100nF 100V")
      (footprint "eagle-import:EIA0603")
      (libsource (lib "eagle-import") (part "C_0603EIA0603"))
    )
    (comp (ref "C28")
      (value "100nF 100V")
      (footprint "eagle-import:EIA0603")
      (libsource (lib "eagle-import") (part "C_0603EIA0603"))
    )
    (comp (ref "C29")
      (value "100nF 100V")
      (footprint "eagle-import:EIA0603")
      (libsource (lib "eagle-import") (part "C_0603EIA0603"))
    )
    (comp (ref "C30")
      (value "100nF 100V")
      (footprint "eagle-import:EIA0603")
      (libsource (lib "eagle-import") (part "C_0603EIA0603"))
    )
    (comp (ref "C31")
      (value "100nF 100V")
      (footprint "eagle-import:EIA0603")
      (libsource (lib "eagle-import") (part "C_0603EIA0603"))
    )
    (comp (ref "C32")
      (value "50PX470MEFC10X20")
      (footprint "eagle-import:CAPACITOR-ELKO-RM5-10X16")
      (fields (field (name "MFR") "Rubicon"))
      (libsource (lib "eagle-import") (part "50PX470MEFC10X20"))
    )
    (comp (ref "C33")
      (value "50PX470MEFC10X20")
      (footprint "eagle-import:CAPACITOR-ELKO-RM5-10X16")
      (fields (field (name "MFR") "Rubicon"))
      (libsource (lib "eagle-import") (part "50PX470MEFC10X20"))
    )
    (comp (ref "C34")
      (value "50PX470MEFC10X20")
      (footprint "eagle-import:CAPACITOR-ELKO-RM5-10X16")
      (fields (field (name "MFR") "Rubicon"))
      (libsource (lib "eagle-import") (part "50PX470MEFC10X20"))
    )
    (comp (ref "C38")
      (value "100nF 100V")
      (footprint "eagle-import:EIA0603")
      (libsource (lib "eagle-import") (part "C_0603EIA0603"))
    )
    (comp (ref "C39")
      (value "1uF/35V")
      (footprint "eagle-import:EIA0603")
      (libsource (lib "eagle-import") (part "C_0603EIA0603"))
    )
    (comp (ref "C40")
      (value "100nF 100V")
      (footprint "eagle-import:EIA0603")
      (libsource (lib "eagle-import") (part "C_0603EIA0603"))
    )
    (comp (ref "C41")
      (value "50PX470MEFC10X20")
      (footprint "eagle-import:CAPACITOR-ELKO-RM5-10X16")
      (fields (field (name "MFR") "Rubicon"))
      (libsource (lib "eagle-import") (part "50PX470MEFC10X20"))
    )
    (comp (ref "C42")
      (value "1uF/35V")
      (footprint "eagle-import:EIA0603")
      (libsource (lib "eagle-import") (part "C_0603EIA0603"))
    )
    (comp (ref "C43")
      (value "100nF 100V")
      (footprint "eagle-import:EIA0603")
      (libsource (lib "eagle-import") (part "C_0603EIA0603"))
    )
    (comp (ref "C44")
      (value "1uF/35V")
      (footprint "eagle-import:EIA0603")
      (libsource (lib "eagle-import") (part "C_0603EIA0603"))
    )
    (comp (ref "C45")
      (value "100nF 100V")
      (footprint "eagle-import:EIA0603")
      (libsource (lib "eagle-import") (part "C_0603EIA0603"))
    )
    (comp (ref "C46")
      (value "1uF/35V")
      (footprint "eagle-import:EIA0603")
      (libsource (lib "eagle-import") (part "C_0603EIA0603"))
    )
    (comp (ref "F1")
      (value "696101000002")
      (footprint "eagle-import:FUSE_RM22.6")
      (fields (field (name "MFR") "Wurth Elektronik"))
      (libsource (lib "eagle-import") (part "696101000002"))
    )
    (comp (ref "IC11")
      (value "TPS54202DDCR")
      (footprint "eagle-import:SOT23-6")
      (fields (field (name "MFR") "Texas Instruments"))
      (libsource (lib "eagle-import") (part "TPS54202DDCR"))
    )
    (comp (ref "IC12")
      (value "LD117AS50TR")
      (footprint "eagle-import:SOT223")
      (libsource (lib "eagle-import") (part "LD117A?S50TR"))
    )
    (comp (ref "IC13")
      (value "LD117AS33TR")
      (footprint "eagle-import:SOT223")
      (libsource (lib "eagle-import") (part "LD117A?S33TR"))
    )
    (comp (ref "J2")
      (value "61300411121")
      (footprint "eagle-import:X04_100MIL_1ROW")
      (fields (field (name "MFR") "Wurth Electronics"))
      (libsource (lib "eagle-import") (part "61300411121"))
    )
    (comp (ref "L2")
      (value "SRN8040TA-220M")
      (footprint "eagle-import:SRN8040TA-220M")
      (fields (field (name "MFR") "Bourns"))
      (libsource (lib "eagle-import") (part "SRN8040TA-220M"))
    )
    (comp (ref "R22")
      (value "100R 1%")
      (footprint "eagle-import:EIA0603")
      (libsource (lib "eagle-import") (part "R_0603"))
    )
    (comp (ref "R25")
      (value "10k 1%")
      (footprint "eagle-import:EIA0603")
      (libsource (lib "eagle-import") (part "R_0603"))
    )
    (comp (ref "R80")
      (value "10k 1%")
      (footprint "eagle-import:EIA0603")
      (libsource (lib "eagle-import") (part "R_0603"))
    )
    (comp (ref "R81")
      (value "1k 1%")
      (footprint "eagle-import:EIA0603")
      (libsource (lib "eagle-import") (part "R_0603"))
    )
    (comp (ref "R82")
      (value "10k 1%")
      (footprint "eagle-import:EIA0603")
      (libsource (lib "eagle-import") (part "R_0603"))
    )
    (comp (ref "R84")
      (value "100R 1%")
      (footprint "eagle-import:EIA0603")
      (libsource (lib "eagle-import") (part "R_0603"))
    )
    (comp (ref "R101")
      (value "100k 1%")
      (footprint "eagle-import:EIA0603")
      (libsource (lib "eagle-import") (part "R_0603"))
    )
    (comp (ref "R102")
      (value "4.3K 1%")
      (footprint "eagle-import:EIA0603")
      (libsource (lib "eagle-import") (part "R_0603"))
    )
    (comp (ref "V4")
      (value "0603ESDA-24NSMD")
      (footprint "eagle-import:EIA0603")
      (fields (field (name "MFR") "Bourns"))
      (libsource (lib "eagle-import") (part "0603ESDA-24NSMD"))
    )
    (comp (ref "V8")
      (value "0603ESDA-24NSMD")
      (footprint "eagle-import:EIA0603")
      (fields (field (name "MFR") "Bourns"))
      (libsource (lib "eagle-import") (part "0603ESDA-24NSMD"))
    )
    (comp (ref "X1")
      (value "B2B-XH-AM(LF)(SN)")
      (footprint "eagle-import:B2B-XH-AM(LF)(SN)")
      (fields (field (name "MFR") "JST"))
      (libsource (lib "eagle-import") (part "B2B-XH-AM(LF)(SN)"))
    )
    (comp (ref "X2")
      (value "B2B-XH-AM(LF)(SN)")
      (footprint "eagle-import:B2B-XH-AM(LF)(SN)")
      (fields (field (name "MFR") "JST"))
      (libsource (lib "eagle-import") (part "B2B-XH-AM(LF)(SN)"))
    )
    (comp (ref "X4")
      (value "282834-2")
      (footprint "eagle-import:TE_282834-2_0")
      (fields (field (name "MFR") "TE"))
      (libsource (lib "eagle-import") (part "282834-2"))
    )
    (comp (ref "X5")
      (value "726386-2TE_726386-2")
      (footprint "eagle-import:TE_726386-2")
      (fields
        (field (name "DIGIKEY_PART_NUMBER") "A114371-ND")
        (field (name "MF") "TE")
        (field (name "MOUSER_PART_NUMBER") "571-726386-2")
      )
      (libsource (lib "eagle-import") (part "726386-2TE_726386-2"))
    )
    (comp (ref "X6")
      (value "282834-2")
      (footprint "eagle-import:TE_282834-2_0")
      (fields (field (name "MFR") "TE"))
      (libsource (lib "eagle-import") (part "282834-2"))
    )
    (comp (ref "X7")
      (value "726386-2TE_726386-2")
      (footprint "eagle-import:TE_726386-2")
      (fields
        (field (name "DIGIKEY_PART_NUMBER") "A114371-ND")
        (field (name "MF") "TE")
        (field (name "MOUSER_PART_NUMBER") "571-726386-2")
      )
      (libsource (lib "eagle-import") (part "726386-2TE_726386-2"))
    )
    (comp (ref "X10")
      (value "726386-2TE_726386-2")
      (footprint "eagle-import:TE_726386-2")
      (fields
        (field (name "DIGIKEY_PART_NUMBER") "A114371-ND")
        (field (name "MF") "TE")
        (field (name "MOUSER_PART_NUMBER") "571-726386-2")
      )
      (libsource (lib "eagle-import") (part "726386-2TE_726386-2"))
    )
    (comp (ref "X11")
      (value "726386-2TE_726386-2")
      (footprint "eagle-import:TE_726386-2")
      (fields
        (field (name "DIGIKEY_PART_NUMBER") "A114371-ND")
        (field (name "MF") "TE")
        (field (name "MOUSER_PART_NUMBER") "571-726386-2")
      )
      (libsource (lib "eagle-import") (part "726386-2TE_726386-2"))
    )
    (comp (ref "X12")
      (value "726386-2TE_726386-2")
      (footprint "eagle-import:TE_726386-2")
      (fields
        (field (name "DIGIKEY_PART_NUMBER") "A114371-ND")
        (field (name "MF") "TE")
        (field (name "MOUSER_PART_NUMBER") "571-726386-2")
      )
      (libsource (lib "eagle-import") (part "726386-2TE_726386-2"))
    )
    (comp (ref "X13")
      (value "726386-2TE_726386-2")
      (footprint "eagle-import:TE_726386-2")
      (fields
        (field (name "DIGIKEY_PART_NUMBER") "A114371-ND")
        (field (name "MF") "TE")
        (field (name "MOUSER_PART_NUMBER") "571-726386-2")
      )
      (libsource (lib "eagle-import") (part "726386-2TE_726386-2"))
    )
    (comp (ref "X14")
      (value "726386-2TE_726386-2")
      (footprint "eagle-import:TE_726386-2")
      (fields
        (field (name "DIGIKEY_PART_NUMBER") "A114371-ND")
        (field (name "MF") "TE")
        (field (name "MOUSER_PART_NUMBER") "571-726386-2")
      )
      (libsource (lib "eagle-import") (part "726386-2TE_726386-2"))
    )
    (comp (ref "X15")
      (value "726386-2TE_726386-2")
      (footprint "eagle-import:TE_726386-2")
      (fields
        (field (name "DIGIKEY_PART_NUMBER") "A114371-ND")
        (field (name "MF") "TE")
        (field (name "MOUSER_PART_NUMBER") "571-726386-2")
      )
      (libsource (lib "eagle-import") (part "726386-2TE_726386-2"))
    )
    (comp (ref "X23")
      (value "282834-2")
      (footprint "eagle-import:TE_282834-2_0")
      (fields (field (name "MFR") "TE"))
      (libsource (lib "eagle-import") (part "282834-2"))
    )
    (comp (ref "C24")
      (value "100nF/50V")
      (footprint "eagle-import:EIA0603")
      (libsource (lib "eagle-import") (part "C_0603EIA0603"))
    )
    (comp (ref "C25")
      (value "100nF")
      (footprint "eagle-import:EIA0603")
      (libsource (lib "eagle-import") (part "C_0603EIA0603"))
    )
    (comp (ref "C35")
      (value "100pF 100V")
      (footprint "eagle-import:EIA0603")
      (libsource (lib "eagle-import") (part "C_0603EIA0603"))
    )
    (comp (ref "C36")
      (value "100nF/50V")
      (footprint "eagle-import:EIA0603")
      (libsource (lib "eagle-import") (part "C_0603EIA0603"))
    )
    (comp (ref "C37")
      (value "100nF/50V")
      (footprint "eagle-import:EIA0603")
      (libsource (lib "eagle-import") (part "C_0603EIA0603"))
    )
    (comp (ref "IC10")
      (value "SN65HVD3082EDR")
      (footprint "eagle-import:SOIC8")
      (fields (field (name "MFR") "TI,3Peak"))
      (libsource (lib "eagle-import") (part "SN65HVD3082EDR"))
    )
    (comp (ref "J3")
      (value "615008148521")
      (footprint "eagle-import:615008148521")
      (fields (field (name "MFR") "Wurth Elektronik"))
      (libsource (lib "eagle-import") (part "615008148521"))
    )
    (comp (ref "J4")
      (value "61300411121")
      (footprint "eagle-import:X04_100MIL_1ROW")
      (fields (field (name "MFR") "Wurth Electronics"))
      (libsource (lib "eagle-import") (part "61300411121"))
    )
    (comp (ref "R20")
      (value "0R 1%")
      (footprint "eagle-import:EIA0603")
      (libsource (lib "eagle-import") (part "R_0603"))
    )
    (comp (ref "R21")
      (value "0R 1%")
      (footprint "eagle-import:EIA0603")
      (libsource (lib "eagle-import") (part "R_0603"))
    )
    (comp (ref "R61")
      (value "0R 1%")
      (footprint "eagle-import:EIA0603")
      (libsource (lib "eagle-import") (part "R_0603"))
    )
    (comp (ref "R62")
      (value "0R 1%")
      (footprint "eagle-import:EIA0603")
      (libsource (lib "eagle-import") (part "R_0603"))
    )
    (comp (ref "R63")
      (value "0R 1%")
      (footprint "eagle-import:EIA0603")
      (libsource (lib "eagle-import") (part "R_0603"))
    )
    (comp (ref "R64")
      (value "10K 1%")
      (footprint "eagle-import:EIA0603")
      (libsource (lib "eagle-import") (part "R_0603"))
    )
    (comp (ref "R65")
      (value "10K")
      (footprint "eagle-import:EIA0603")
      (libsource (lib "eagle-import") (part "R_0603"))
    )
    (comp (ref "R66")
      (value "0R 1%")
      (footprint "eagle-import:EIA0603")
      (libsource (lib "eagle-import") (part "R_0603"))
    )
    (comp (ref "R67")
      (value "0R 1%")
      (footprint "eagle-import:EIA0603")
      (libsource (lib "eagle-import") (part "R_0603"))
    )
    (comp (ref "R68")
      (value "0R 1%")
      (footprint "eagle-import:EIA0603")
      (libsource (lib "eagle-import") (part "R_0603"))
    )
    (comp (ref "R69")
      (value "10K 1%")
      (footprint "eagle-import:EIA0603")
      (libsource (lib "eagle-import") (part "R_0603"))
    )
    (comp (ref "R70")
      (value "10K")
      (footprint "eagle-import:EIA0603")
      (libsource (lib "eagle-import") (part "R_0603"))
    )
    (comp (ref "R90")
      (value "1K 1%")
      (footprint "eagle-import:EIA0603")
      (libsource (lib "eagle-import") (part "R_0603"))
    )
    (comp (ref "R92")
      (value "0R 1%")
      (footprint "eagle-import:EIA0603")
      (libsource (lib "eagle-import") (part "R_0603"))
    )
    (comp (ref "R93")
      (value "1K 1%")
      (footprint "eagle-import:EIA0603")
      (libsource (lib "eagle-import") (part "R_0603"))
    )
    (comp (ref "R94")
      (value "1.8K 1%")
      (footprint "eagle-import:EIA0603")
      (libsource (lib "eagle-import") (part "R_0603"))
    )
    (comp (ref "R95")
      (value "470R 1%")
      (footprint "eagle-import:EIA0603")
      (libsource (lib "eagle-import") (part "R_0603"))
    )
    (comp (ref "R96")
      (value "0R 1%")
      (footprint "eagle-import:EIA0603")
      (libsource (lib "eagle-import") (part "R_0603"))
    )
    (comp (ref "R97")
      (value "470R 1%")
      (footprint "eagle-import:EIA0603")
      (libsource (lib "eagle-import") (part "R_0603"))
    )
    (comp (ref "R98")
      (value "470R 1%")
      (footprint "eagle-import:EIA0603")
      (libsource (lib "eagle-import") (part "R_0603"))
    )
    (comp (ref "R99")
      (value "100R 1%")
      (footprint "eagle-import:EIA0603")
      (libsource (lib "eagle-import") (part "R_0603"))
    )
    (comp (ref "R100")
      (value "100R 1%")
      (footprint "eagle-import:EIA0603")
      (libsource (lib "eagle-import") (part "R_0603"))
    )
    (comp (ref "V9")
      (value "0603ESDA-24NSMD")
      (footprint "eagle-import:EIA0603")
      (fields (field (name "MFR") "Bourns"))
      (libsource (lib "eagle-import") (part "0603ESDA-24NSMD"))
    )
    (comp (ref "V10")
      (value "0603ESDA-24NSMD")
      (footprint "eagle-import:EIA0603")
      (fields (field (name "MFR") "Bourns"))
      (libsource (lib "eagle-import") (part "0603ESDA-24NSMD"))
    )
    (comp (ref "X8")
      (value "5-102203-3")
      (footprint "eagle-import:TE_5-102203-3")
      (fields (field (name "MFR") "TE Connectivity"))
      (libsource (lib "eagle-import") (part "5-102203-3"))
    )
    (comp (ref "X9")
      (value "5-102203-3")
      (footprint "eagle-import:TE_5-102203-3")
      (fields (field (name "MFR") "TE Connectivity"))
      (libsource (lib "eagle-import") (part "5-102203-3"))
    )
    (comp (ref "X17")
      (value "282834-3")
      (footprint "eagle-import:TE_282834-3_0")
      (fields (field (name "MFR") "TE"))
      (libsource (lib "eagle-import") (part "282834-3"))
    )
    (comp (ref "X18")
      (value "282834-3")
      (footprint "eagle-import:TE_282834-3_0")
      (fields (field (name "MFR") "TE"))
      (libsource (lib "eagle-import") (part "282834-3"))
    )
    (comp (ref "X24")
      (value "282834-3")
      (footprint "eagle-import:TE_282834-3_0")
      (fields (field (name "MFR") "TE"))
      (libsource (lib "eagle-import") (part "282834-3"))
    )
  )
  (nets
    (net (code "1") (name "AIR_PUMP+") (class "Default")
      (node (ref "D1") (pin "1") (pinfunction "C_1") (pintype "passive"))
      (node (ref "Q2") (pin "2") (pinfunction "DRAIN_2") (pintype "passive"))
      (node (ref "Q2") (pin "4") (pinfunction "DRAIN_4") (pintype "passive"))
      (node (ref "R30") (pin "2") (pinfunction "2_2") (pintype "passive"))
      (node (ref "X5") (pin "1") (pinfunction "1_1") (pintype "passive"))
      (node (ref "X5") (pin "1-2") (pinfunction "1_1-2") (pintype "passive"))
    )
    (net (code "2") (name "AI_O2_SENSOR1") (class "Default")
      (node (ref "C22") (pin "2") (pinfunction "2_2") (pintype "passive"))
      (node (ref "IC1") (pin "17") (pinfunction "PA0_17") (pintype "bidirectional"))
      (node (ref "R38") (pin "1") (pinfunction "1_1") (pintype "passive"))
      (node (ref "R39") (pin "1") (pinfunction "1_1") (pintype "passive"))
    )
    (net (code "3") (name "AI_O2_SENSOR2") (class "Default")
      (node (ref "C23") (pin "2") (pinfunction "2_2") (pintype "passive"))
      (node (ref "IC1") (pin "18") (pinfunction "PA1_18") (pintype "bidirectional"))
      (node (ref "R52") (pin "1") (pinfunction "1_1") (pintype "passive"))
      (node (ref "R53") (pin "1") (pinfunction "1_1") (pintype "passive"))
    )
    (net (code "4") (name "CO2_SCL") (class "Default")
      (node (ref "IC1") (pin "13") (pinfunction "PC0_13") (pintype "bidirectional"))
      (node (ref "R21") (pin "1") (pinfunction "1_1") (pintype "passive"))
      (node (ref "R60") (pin "1") (pinfunction "1_1") (pintype "passive"))
      (node (ref "R63") (pin "1") (pinfunction "1_1") (pintype "passive"))
      (node (ref "R68") (pin "1") (pinfunction "1_1") (pintype "passive"))
    )
    (net (code "5") (name "CO2_SDA") (class "Default")
      (node (ref "IC1") (pin "14") (pinfunction "PC1_14") (pintype "bidirectional"))
      (node (ref "R20") (pin "1") (pinfunction "1_1") (pintype "passive"))
      (node (ref "R59") (pin "1") (pinfunction "1_1") (pintype "passive"))
      (node (ref "R62") (pin "1") (pinfunction "1_1") (pintype "passive"))
      (node (ref "R67") (pin "1") (pinfunction "1_1") (pintype "passive"))
    )
    (net (code "6") (name "DGB_SWDCLK_TCK") (class "Default")
      (node (ref "IC1") (pin "46") (pinfunction "PA14-BOOT0_46") (pintype "bidirectional"))
      (node (ref "R17") (pin "2") (pinfunction "2_2") (pintype "passive"))
    )
    (net (code "7") (name "DGB_SWDIO_TMS") (class "Default")
      (node (ref "IC1") (pin "45") (pinfunction "PA13_45") (pintype "bidirectional"))
      (node (ref "R16") (pin "2") (pinfunction "2_2") (pintype "passive"))
    )
    (net (code "8") (name "DI_PULSE1") (class "Default")
      (node (ref "IC1") (pin "37") (pinfunction "PA9_37") (pintype "bidirectional"))
      (node (ref "R15") (pin "1") (pinfunction "1_1") (pintype "passive"))
    )
    (net (code "9") (name "DI_PUSHBUTTON1") (class "Default")
      (node (ref "IC1") (pin "27") (pinfunction "PB0_27") (pintype "bidirectional"))
      (node (ref "R22") (pin "1") (pinfunction "1_1") (pintype "passive"))
    )
    (net (code "10") (name "DI_PUSHBUTTON2") (class "Default")
      (node (ref "IC1") (pin "26") (pinfunction "PC5_26") (pintype "bidirectional"))
      (node (ref "R84") (pin "1") (pinfunction "1_1") (pintype "passive"))
    )
    (net (code "11") (name "DI_USART_RX") (class "Default")
      (node (ref "IC1") (pin "1") (pinfunction "PC11_1") (pintype "bidirectional"))
      (node (ref "R95") (pin "2") (pinfunction "2_2") (pintype "passive"))
    )
    (net (code "12") (name "DO_AIR_PUMP_ON") (class "Default")
      (node (ref "IC1") (pin "48") (pinfunction "PC8_48") (pintype "bidirectional"))
      (node (ref "R29") (pin "2") (pinfunction "2_2") (pintype "passive"))
    )
    (net (code "13") (name "DO_FAN_ON") (class "Default")
      (node (ref "IC1") (pin "51") (pinfunction "PD1_51") (pintype "bidirectional"))
      (node (ref "R85") (pin "2") (pinfunction "2_2") (pintype "passive"))
    )
    (net (code "14") (name "DO_HEATER_ON") (class "Default")
      (node (ref "IC1") (pin "2") (pinfunction "PC12_2") (pintype "bidirectional"))
      (node (ref "R74") (pin "2") (pinfunction "2_2") (pintype "passive"))
    )
    (net (code "15") (name "DO_HUMIDIFIER_ON") (class "Default")
      (node (ref "IC1") (pin "3") (pinfunction "PC13_3") (pintype "bidirectional"))
      (node (ref "R77") (pin "2") (pinfunction "2_2") (pintype "passive"))
    )
    (net (code "16") (name "DO_IR_TX") (class "Default")
      (node (ref "IC1") (pin "36") (pinfunction "PA8_36") (pintype "bidirectional"))
      (node (ref "R3") (pin "2") (pinfunction "2_2") (pintype "passive"))
    )
    (net (code "17") (name "DO_USART_TX") (class "Default")
      (node (ref "IC1") (pin "64") (pinfunction "PC10_64") (pintype "bidirectional"))
      (node (ref "R98") (pin "2") (pinfunction "2_2") (pintype "passive"))
    )
    (net (code "18") (name "DO_USART_TX_EN") (class "Default")
      (node (ref "IC1") (pin "47") (pinfunction "PA15_47") (pintype "bidirectional"))
      (node (ref "R97") (pin "2") (pinfunction "2_2") (pintype "passive"))
    )
    (net (code "19") (name "FAN+") (class "Default")
      (node (ref "D6") (pin "1") (pinfunction "C_1") (pintype "passive"))
      (node (ref "Q8") (pin "2") (pinfunction "DRAIN_2") (pintype "passive"))
      (node (ref "Q8") (pin "4") (pinfunction "DRAIN_4") (pintype "passive"))
      (node (ref "R89") (pin "2") (pinfunction "2_2") (pintype "passive"))
      (node (ref "X23") (pin "1") (pinfunction "1_1") (pintype "bidirectional"))
    )
    (net (code "20") (name "GND") (class "Default")
      (node (ref "BT1") (pin "N") (pinfunction "NEG_N") (pintype "passive"))
      (node (ref "C1") (pin "1") (pinfunction "1_1") (pintype "passive"))
      (node (ref "C10") (pin "2") (pinfunction "2_2") (pintype "passive"))
      (node (ref "C12") (pin "2") (pinfunction "2_2") (pintype "passive"))
      (node (ref "C13") (pin "1") (pinfunction "1_1") (pintype "passive"))
      (node (ref "C14") (pin "1") (pinfunction "1_1") (pintype "passive"))
      (node (ref "C16") (pin "2") (pinfunction "2_2") (pintype "passive"))
      (node (ref "C18") (pin "2") (pinfunction "2_2") (pintype "passive"))
      (node (ref "C2") (pin "1") (pinfunction "1_1") (pintype "passive"))
      (node (ref "C22") (pin "1") (pinfunction "1_1") (pintype "passive"))
      (node (ref "C23") (pin "1") (pinfunction "1_1") (pintype "passive"))
      (node (ref "C24") (pin "1") (pinfunction "1_1") (pintype "passive"))
      (node (ref "C25") (pin "1") (pinfunction "1_1") (pintype "passive"))
      (node (ref "C26") (pin "2") (pinfunction "2_2") (pintype "passive"))
      (node (ref "C27") (pin "2") (pinfunction "2_2") (pintype "passive"))
      (node (ref "C28") (pin "2") (pinfunction "2_2") (pintype "passive"))
      (node (ref "C29") (pin "2") (pinfunction "2_2") (pintype "passive"))
      (node (ref "C3") (pin "2") (pinfunction "2_2") (pintype "passive"))
      (node (ref "C30") (pin "2") (pinfunction "2_2") (pintype "passive"))
      (node (ref "C31") (pin "2") (pinfunction "2_2") (pintype "passive"))
      (node (ref "C32") (pin "2") (pinfunction "-_2") (pintype "passive"))
      (node (ref "C33") (pin "2") (pinfunction "-_2") (pintype "passive"))
      (node (ref "C34") (pin "2") (pinfunction "-_2") (pintype "passive"))
      (node (ref "C35") (pin "1") (pinfunction "1_1") (pintype "passive"))
      (node (ref "C36") (pin "2") (pinfunction "2_2") (pintype "passive"))
      (node (ref "C37") (pin "2") (pinfunction "2_2") (pintype "passive"))
      (node (ref "C39") (pin "2") (pinfunction "2_2") (pintype "passive"))
      (node (ref "C4") (pin "1") (pinfunction "1_1") (pintype "passive"))
      (node (ref "C40") (pin "2") (pinfunction "2_2") (pintype "passive"))
      (node (ref "C41") (pin "2") (pinfunction "-_2") (pintype "passive"))
      (node (ref "C42") (pin "2") (pinfunction "2_2") (pintype "passive"))
      (node (ref "C43") (pin "2") (pinfunction "2_2") (pintype "passive"))
      (node (ref "C44") (pin "2") (pinfunction "2_2") (pintype "passive"))
      (node (ref "C45") (pin "2") (pinfunction "2_2") (pintype "passive"))
      (node (ref "C46") (pin "2") (pinfunction "2_2") (pintype "passive"))
      (node (ref "C47") (pin "2") (pinfunction "2_2") (pintype "passive"))
      (node (ref "C48") (pin "2") (pinfunction "2_2") (pintype "passive"))
      (node (ref "C49") (pin "2") (pinfunction "2_2") (pintype "passive"))
      (node (ref "C5") (pin "1") (pinfunction "1_1") (pintype "passive"))
      (node (ref "C50") (pin "2") (pinfunction "2_2") (pintype "passive"))
      (node (ref "C51") (pin "1") (pinfunction "1_1") (pintype "passive"))
      (node (ref "C52") (pin "1") (pinfunction "1_1") (pintype "passive"))
      (node (ref "C6") (pin "2") (pinfunction "2_2") (pintype "passive"))
      (node (ref "C7") (pin "2") (pinfunction "2_2") (pintype "passive"))
      (node (ref "C8") (pin "2") (pinfunction "2_2") (pintype "passive"))
      (node (ref "C9") (pin "2") (pinfunction "2_2") (pintype "passive"))
      (node (ref "D1") (pin "2") (pinfunction "A_2") (pintype "passive"))
      (node (ref "D2") (pin "2") (pinfunction "A_2") (pintype "passive"))
      (node (ref "D4") (pin "2") (pinfunction "A_2") (pintype "passive"))
      (node (ref "D6") (pin "2") (pinfunction "A_2") (pintype "passive"))
      (node (ref "IC1") (pin "9") (pinfunction "VSS/VSSA_9") (pintype "bidirectional"))
      (node (ref "IC10") (pin "5") (pinfunction "GND_5") (pintype "bidirectional"))
      (node (ref "IC11") (pin "1") (pinfunction "GND_1") (pintype "bidirectional"))
      (node (ref "IC12") (pin "1") (pinfunction "ADJ_1") (pintype "input"))
      (node (ref "IC13") (pin "1") (pinfunction "ADJ_1") (pintype "input"))
      (node (ref "IC15") (pin "2") (pinfunction "VEE_2") (pintype "passive"))
      (node (ref "IC2") (pin "2") (pinfunction "GND_2") (pintype "power_in"))
      (node (ref "IC3") (pin "2") (pinfunction "NULL_2") (pintype "passive"))
      (node (ref "IC4") (pin "2") (pinfunction "VEE_2") (pintype "passive"))
      (node (ref "IC5") (pin "2") (pinfunction "VEE_2") (pintype "passive"))
      (node (ref "IC6") (pin "2") (pinfunction "VEE_2") (pintype "passive"))
      (node (ref "IC7") (pin "2") (pinfunction "VEE_2") (pintype "passive"))
      (node (ref "IC8") (pin "2") (pinfunction "VEE_2") (pintype "passive"))
      (node (ref "J1") (pin "5") (pinfunction "GND_5") (pintype "power_in"))
      (node (ref "J1") (pin "SH1") (pinfunction "SHIELD1_SH1") (pintype "passive"))
      (node (ref "J1") (pin "SH2") (pinfunction "SHIELD2_SH2") (pintype "passive"))
      (node (ref "J1") (pin "SH3") (pinfunction "SHIELD3_SH3") (pintype "passive"))
      (node (ref "J1") (pin "SH4") (pinfunction "SHIELD4_SH4") (pintype "passive"))
      (node (ref "J1") (pin "SH5") (pinfunction "SHIELD5_SH5") (pintype "passive"))
      (node (ref "J1") (pin "SH6") (pinfunction "SHIELD6_SH6") (pintype "passive"))
      (node (ref "J2") (pin "03") (pinfunction "03_03") (pintype "passive"))
      (node (ref "J3") (pin "8") (pinfunction "8_8") (pintype "passive"))
      (node (ref "J4") (pin "04") (pinfunction "04_04") (pintype "passive"))
      (node (ref "K1") (pin "A1") (pinfunction "1_A1") (pintype "passive"))
      (node (ref "K2") (pin "A1") (pinfunction "1_A1") (pintype "passive"))
      (node (ref "Q1") (pin "2") (pinfunction "E_2") (pintype "passive"))
      (node (ref "Q3") (pin "2") (pinfunction "S_2") (pintype "passive"))
      (node (ref "Q5") (pin "2") (pinfunction "S_2") (pintype "passive"))
      (node (ref "Q7") (pin "2") (pinfunction "S_2") (pintype "passive"))
      (node (ref "Q9") (pin "2") (pinfunction "S_2") (pintype "passive"))
      (node (ref "R1") (pin "2") (pinfunction "2_2") (pintype "passive"))
      (node (ref "R102") (pin "1") (pinfunction "1_1") (pintype "passive"))
      (node (ref "R106") (pin "2") (pinfunction "2_2") (pintype "passive"))
      (node (ref "R11") (pin "2") (pinfunction "2_2") (pintype "passive"))
      (node (ref "R12") (pin "1") (pinfunction "1_1") (pintype "passive"))
      (node (ref "R28") (pin "1") (pinfunction "1_1") (pintype "passive"))
      (node (ref "R30") (pin "1") (pinfunction "1_1") (pintype "passive"))
      (node (ref "R31") (pin "1") (pinfunction "1_1") (pintype "passive"))
      (node (ref "R39") (pin "2") (pinfunction "2_2") (pintype "passive"))
      (node (ref "R4") (pin "2") (pinfunction "2_2") (pintype "passive"))
      (node (ref "R41") (pin "2") (pinfunction "2_2") (pintype "passive"))
      (node (ref "R45") (pin "1") (pinfunction "1_1") (pintype "passive"))
      (node (ref "R53") (pin "2") (pinfunction "2_2") (pintype "passive"))
      (node (ref "R61") (pin "1") (pinfunction "1_1") (pintype "passive"))
      (node (ref "R64") (pin "2") (pinfunction "2_2") (pintype "passive"))
      (node (ref "R65") (pin "2") (pinfunction "2_2") (pintype "passive"))
      (node (ref "R66") (pin "1") (pinfunction "1_1") (pintype "passive"))
      (node (ref "R69") (pin "2") (pinfunction "2_2") (pintype "passive"))
      (node (ref "R70") (pin "2") (pinfunction "2_2") (pintype "passive"))
      (node (ref "R71") (pin "1") (pinfunction "1_1") (pintype "passive"))
      (node (ref "R72") (pin "1") (pinfunction "1_1") (pintype "passive"))
      (node (ref "R78") (pin "1") (pinfunction "1_1") (pintype "passive"))
      (node (ref "R79") (pin "1") (pinfunction "1_1") (pintype "passive"))
      (node (ref "R8") (pin "1") (pinfunction "1_1") (pintype "passive"))
      (node (ref "R82") (pin "2") (pinfunction "2_2") (pintype "passive"))
      (node (ref "R88") (pin "1") (pinfunction "1_1") (pintype "passive"))
      (node (ref "R89") (pin "1") (pinfunction "1_1") (pintype "passive"))
      (node (ref "R92") (pin "1") (pinfunction "1_1") (pintype "passive"))
      (node (ref "R94") (pin "1") (pinfunction "1_1") (pintype "passive"))
      (node (ref "V1") (pin "1") (pinfunction "1_1") (pintype "passive"))
      (node (ref "V10") (pin "1") (pinfunction "1_1") (pintype "passive"))
      (node (ref "V2") (pin "1") (pinfunction "1_1") (pintype "passive"))
      (node (ref "V4") (pin "2") (pinfunction "2_2") (pintype "passive"))
      (node (ref "V8") (pin "2") (pinfunction "2_2") (pintype "passive"))
      (node (ref "V9") (pin "1") (pinfunction "1_1") (pintype "passive"))
      (node (ref "X10") (pin "1") (pinfunction "1_1") (pintype "passive"))
      (node (ref "X10") (pin "1-2") (pinfunction "1_1-2") (pintype "passive"))
      (node (ref "X12") (pin "1") (pinfunction "1_1") (pintype "passive"))
      (node (ref "X12") (pin "1-2") (pinfunction "1_1-2") (pintype "passive"))
      (node (ref "X14") (pin "1") (pinfunction "1_1") (pintype "passive"))
      (node (ref "X14") (pin "1-2") (pinfunction "1_1-2") (pintype "passive"))
      (node (ref "X23") (pin "2") (pinfunction "2_2") (pintype "bidirectional"))
      (node (ref "X3") (pin "4") (pinfunction "4_4") (pintype "bidirectional"))
      (node (ref "X4") (pin "2") (pinfunction "2_2") (pintype "bidirectional"))
      (node (ref "X6") (pin "2") (pinfunction "2_2") (pintype "bidirectional"))
      (node (ref "X7") (pin "1") (pinfunction "1_1") (pintype "passive"))
      (node (ref "X7") (pin "1-2") (pinfunction "1_1-2") (pintype "passive"))
      (node (ref "X8") (pin "4") (pinfunction "4_4") (pintype "passive"))
      (node (ref "X9") (pin "4") (pinfunction "4_4") (pintype "passive"))
    )
    (net (code "21") (name "HEATER+") (class "Default")
      (node (ref "K1") (pin "14") (pinfunction "3_14") (pintype "passive"))
      (node (ref "V6") (pin "2") (pinfunction "2_2") (pintype "passive"))
      (node (ref "X11") (pin "1") (pinfunction "1_1") (pintype "passive"))
      (node (ref "X11") (pin "1-2") (pinfunction "1_1-2") (pintype "passive"))
    )
    (net (code "22") (name "HUMIDIFIER+") (class "Default")
      (node (ref "K2") (pin "14") (pinfunction "3_14") (pintype "passive"))
      (node (ref "V5") (pin "2") (pinfunction "2_2") (pintype "passive"))
      (node (ref "X13") (pin "1") (pinfunction "1_1") (pintype "passive"))
      (node (ref "X13") (pin "1-2") (pinfunction "1_1-2") (pintype "passive"))
    )
    (net (code "23") (name "IR_DIODE_A") (class "Default")
      (node (ref "R5") (pin "1") (pinfunction "1_1") (pintype "passive"))
      (node (ref "R6") (pin "2") (pinfunction "2_2") (pintype "passive"))
      (node (ref "X2") (pin "2") (pinfunction "2_2") (pintype "bidirectional"))
    )
    (net (code "24") (name "IR_DIODE_C") (class "Default")
      (node (ref "Q1") (pin "3") (pinfunction "C_3") (pintype "passive"))
      (node (ref "R5") (pin "2") (pinfunction "2_2") (pintype "passive"))
      (node (ref "X2") (pin "1") (pinfunction "1_1") (pintype "bidirectional"))
    )
    (net (code "25") (name "IR_TR_NPN_C") (class "Default")
      (node (ref "R13") (pin "1") (pinfunction "1_1") (pintype "passive"))
      (node (ref "R9") (pin "1") (pinfunction "1_1") (pintype "passive"))
      (node (ref "V3") (pin "2") (pinfunction "2_2") (pintype "passive"))
      (node (ref "X1") (pin "2") (pinfunction "2_2") (pintype "bidirectional"))
    )
    (net (code "26") (name "IR_TR_NPN_E") (class "Default")
      (node (ref "R12") (pin "2") (pinfunction "2_2") (pintype "passive"))
      (node (ref "R7") (pin "1") (pinfunction "1_1") (pintype "passive"))
      (node (ref "V3") (pin "1") (pinfunction "1_1") (pintype "passive"))
      (node (ref "X1") (pin "1") (pinfunction "1_1") (pintype "bidirectional"))
    )
    (net (code "27") (name "LCD_SCL") (class "Default")
      (node (ref "IC1") (pin "24") (pinfunction "PA7_24") (pintype "bidirectional"))
      (node (ref "J2") (pin "01") (pinfunction "01_01") (pintype "passive"))
      (node (ref "R23") (pin "1") (pinfunction "1_1") (pintype "passive"))
    )
    (net (code "28") (name "LCD_SDA") (class "Default")
      (node (ref "IC1") (pin "23") (pinfunction "PA6_23") (pintype "bidirectional"))
      (node (ref "J2") (pin "02") (pinfunction "02_02") (pintype "passive"))
      (node (ref "R24") (pin "1") (pinfunction "1_1") (pintype "passive"))
    )
    (net (code "29") (name "NRST") (class "Default")
      (node (ref "C5") (pin "2") (pinfunction "2_2") (pintype "passive"))
      (node (ref "IC1") (pin "12") (pinfunction "PF2-NRST_12") (pintype "bidirectional"))
      (node (ref "R18") (pin "2") (pinfunction "2_2") (pintype "passive"))
      (node (ref "R19") (pin "1") (pinfunction "1_1") (pintype "passive"))
    )
    (net (code "30") (name "Net-(BT1-POS)") (class "Default")
      (node (ref "BT1") (pin "P") (pinfunction "POS_P") (pintype "passive"))
      (node (ref "C47") (pin "1") (pinfunction "1_1") (pintype "passive"))
      (node (ref "IC1") (pin "6") (pinfunction "VBAT_6") (pintype "bidirectional"))
    )
    (net (code "31") (name "Net-(C11-Pad2)") (class "Default")
      (node (ref "C11") (pin "2") (pinfunction "2_2") (pintype "passive"))
      (node (ref "R33") (pin "1") (pinfunction "1_1") (pintype "passive"))
      (node (ref "R34") (pin "2") (pinfunction "2_2") (pintype "passive"))
    )
    (net (code "32") (name "Net-(C15-Pad2)") (class "Default")
      (node (ref "C15") (pin "2") (pinfunction "2_2") (pintype "passive"))
      (node (ref "C49") (pin "1") (pinfunction "1_1") (pintype "passive"))
    )
    (net (code "33") (name "Net-(C17-Pad2)") (class "Default")
      (node (ref "C17") (pin "2") (pinfunction "2_2") (pintype "passive"))
      (node (ref "R47") (pin "1") (pinfunction "1_1") (pintype "passive"))
      (node (ref "R48") (pin "2") (pinfunction "2_2") (pintype "passive"))
    )
    (net (code "34") (name "Net-(C19-Pad2)") (class "Default")
      (node (ref "C19") (pin "2") (pinfunction "2_2") (pintype "passive"))
      (node (ref "C48") (pin "1") (pinfunction "1_1") (pintype "passive"))
    )
    (net (code "35") (name "Net-(C35-Pad2)") (class "Default")
      (node (ref "C35") (pin "2") (pinfunction "2_2") (pintype "passive"))
      (node (ref "R100") (pin "1") (pinfunction "1_1") (pintype "passive"))
      (node (ref "R99") (pin "1") (pinfunction "1_1") (pintype "passive"))
    )
    (net (code "36") (name "Net-(D2-C)") (class "Default")
      (node (ref "D2") (pin "1") (pinfunction "C_1") (pintype "passive"))
      (node (ref "K1") (pin "A2") (pinfunction "2_A2") (pintype "passive"))
      (node (ref "Q4") (pin "2") (pinfunction "DRAIN_2") (pintype "passive"))
      (node (ref "Q4") (pin "4") (pinfunction "DRAIN_4") (pintype "passive"))
      (node (ref "R72") (pin "2") (pinfunction "2_2") (pintype "passive"))
    )
    (net (code "37") (name "Net-(D3-A)") (class "Default")
      (node (ref "D3") (pin "1") (pinfunction "A_1") (pintype "passive"))
      (node (ref "Q4") (pin "1") (pinfunction "GATE_1") (pintype "passive"))
      (node (ref "R73") (pin "1") (pinfunction "1_1") (pintype "passive"))
      (node (ref "R75") (pin "2") (pinfunction "2_2") (pintype "passive"))
    )
    (net (code "38") (name "Net-(D4-C)") (class "Default")
      (node (ref "D4") (pin "1") (pinfunction "C_1") (pintype "passive"))
      (node (ref "K2") (pin "A2") (pinfunction "2_A2") (pintype "passive"))
      (node (ref "Q6") (pin "2") (pinfunction "DRAIN_2") (pintype "passive"))
      (node (ref "Q6") (pin "4") (pinfunction "DRAIN_4") (pintype "passive"))
      (node (ref "R79") (pin "2") (pinfunction "2_2") (pintype "passive"))
    )
    (net (code "39") (name "Net-(D5-A)") (class "Default")
      (node (ref "D5") (pin "1") (pinfunction "A_1") (pintype "passive"))
      (node (ref "Q6") (pin "1") (pinfunction "GATE_1") (pintype "passive"))
      (node (ref "R76") (pin "2") (pinfunction "2_2") (pintype "passive"))
      (node (ref "R83") (pin "1") (pinfunction "1_1") (pintype "passive"))
    )
    (net (code "40") (name "Net-(D7-A)") (class "Default")
      (node (ref "D7") (pin "1") (pinfunction "A_1") (pintype "passive"))
      (node (ref "Q8") (pin "1") (pinfunction "GATE_1") (pintype "passive"))
      (node (ref "R86") (pin "1") (pinfunction "1_1") (pintype "passive"))
      (node (ref "R87") (pin "2") (pinfunction "2_2") (pintype "passive"))
    )
    (net (code "41") (name "Net-(D14-A)") (class "Default")
      (node (ref "D14") (pin "1") (pinfunction "A_1") (pintype "passive"))
      (node (ref "Q2") (pin "1") (pinfunction "GATE_1") (pintype "passive"))
      (node (ref "R26") (pin "1") (pinfunction "1_1") (pintype "passive"))
      (node (ref "R27") (pin "2") (pinfunction "2_2") (pintype "passive"))
    )
    (net (code "42") (name "Net-(IC1-PA2)") (class "Default")
      (node (ref "IC1") (pin "19") (pinfunction "PA2_19") (pintype "bidirectional"))
      (node (ref "R91") (pin "2") (pinfunction "2_2") (pintype "passive"))
    )
    (net (code "43") (name "Net-(IC1-PC14-OSC32_IN)") (class "Default")
      (node (ref "C15") (pin "1") (pinfunction "1_1") (pintype "passive"))
      (node (ref "IC1") (pin "4") (pinfunction "PC14-OSC32_IN_4") (pintype "bidirectional"))
      (node (ref "IC14") (pin "1") (pinfunction "1_1") (pintype "passive"))
      (node (ref "IC14") (pin "2") (pinfunction "2_2") (pintype "power_in"))
      (node (ref "R104") (pin "1") (pinfunction "1_1") (pintype "passive"))
    )
    (net (code "44") (name "Net-(IC1-PC15-OSC32_OUT)") (class "Default")
      (node (ref "C19") (pin "1") (pinfunction "1_1") (pintype "passive"))
      (node (ref "IC1") (pin "5") (pinfunction "PC15-OSC32_OUT_5") (pintype "bidirectional"))
      (node (ref "IC14") (pin "3") (pinfunction "3_3") (pintype "passive"))
      (node (ref "IC14") (pin "4") (pinfunction "4_4") (pintype "passive"))
      (node (ref "R104") (pin "2") (pinfunction "2_2") (pintype "passive"))
    )
    (net (code "45") (name "Net-(IC1-PF0-OSC_IN)") (class "Default")
      (node (ref "C1") (pin "2") (pinfunction "2_2") (pintype "passive"))
      (node (ref "IC1") (pin "10") (pinfunction "PF0-OSC_IN_10") (pintype "bidirectional"))
      (node (ref "IC2") (pin "1") (pinfunction "INPUT_1") (pintype "passive"))
      (node (ref "R2") (pin "2") (pinfunction "2_2") (pintype "passive"))
    )
    (net (code "46") (name "Net-(IC1-PF1-OSC_OUT)") (class "Default")
      (node (ref "C2") (pin "2") (pinfunction "2_2") (pintype "passive"))
      (node (ref "IC1") (pin "11") (pinfunction "PF1-OSC_OUT_11") (pintype "bidirectional"))
      (node (ref "IC2") (pin "3") (pinfunction "OUTPUT_3") (pintype "passive"))
      (node (ref "R2") (pin "1") (pinfunction "1_1") (pintype "passive"))
    )
    (net (code "47") (name "Net-(IC3-NULL-Pad1)") (class "Default")
      (node (ref "IC3") (pin "1") (pinfunction "NULL_1") (pintype "passive"))
      (node (ref "R13") (pin "2") (pinfunction "2_2") (pintype "passive"))
      (node (ref "R14") (pin "1") (pinfunction "1_1") (pintype "passive"))
      (node (ref "R7") (pin "2") (pinfunction "2_2") (pintype "passive"))
      (node (ref "R8") (pin "2") (pinfunction "2_2") (pintype "passive"))
    )
    (net (code "48") (name "Net-(IC3-NULL-Pad3)") (class "Default")
      (node (ref "IC3") (pin "3") (pinfunction "NULL_3") (pintype "passive"))
      (node (ref "R10") (pin "1") (pinfunction "1_1") (pintype "passive"))
      (node (ref "R11") (pin "1") (pinfunction "1_1") (pintype "passive"))
    )
    (net (code "49") (name "Net-(IC3-NULL-Pad4)") (class "Default")
      (node (ref "IC3") (pin "4") (pinfunction "NULL_4") (pintype "passive"))
      (node (ref "R14") (pin "2") (pinfunction "2_2") (pintype "passive"))
      (node (ref "R15") (pin "2") (pinfunction "2_2") (pintype "passive"))
    )
    (net (code "50") (name "Net-(IC4-IN-)") (class "Default")
      (node (ref "IC4") (pin "4") (pinfunction "IN-_4") (pintype "passive"))
      (node (ref "R33") (pin "2") (pinfunction "2_2") (pintype "passive"))
    )
    (net (code "51") (name "Net-(IC5-IN+)") (class "Default")
      (node (ref "IC5") (pin "3") (pinfunction "IN+_3") (pintype "passive"))
      (node (ref "R36") (pin "1") (pinfunction "1_1") (pintype "passive"))
    )
    (net (code "52") (name "Net-(IC5-IN-)") (class "Default")
      (node (ref "IC5") (pin "4") (pinfunction "IN-_4") (pintype "passive"))
      (node (ref "R35") (pin "1") (pinfunction "1_1") (pintype "passive"))
      (node (ref "R37") (pin "2") (pinfunction "2_2") (pintype "passive"))
    )
    (net (code "53") (name "Net-(IC5-OUT)") (class "Default")
      (node (ref "IC5") (pin "1") (pinfunction "OUT_1") (pintype "passive"))
      (node (ref "R37") (pin "1") (pinfunction "1_1") (pintype "passive"))
      (node (ref "R38") (pin "2") (pinfunction "2_2") (pintype "passive"))
    )
    (net (code "54") (name "Net-(IC6-IN+)") (class "Default")
      (node (ref "C13") (pin "2") (pinfunction "2_2") (pintype "passive"))
      (node (ref "IC6") (pin "3") (pinfunction "IN+_3") (pintype "passive"))
      (node (ref "R41") (pin "1") (pinfunction "1_1") (pintype "passive"))
      (node (ref "R42") (pin "1") (pinfunction "1_1") (pintype "passive"))
    )
    (net (code "55") (name "Net-(IC6-IN-)") (class "Default")
      (node (ref "IC6") (pin "4") (pinfunction "IN-_4") (pintype "passive"))
      (node (ref "R40") (pin "2") (pinfunction "2_2") (pintype "passive"))
    )
    (net (code "56") (name "Net-(IC6-OUT)") (class "Default")
      (node (ref "IC6") (pin "1") (pinfunction "OUT_1") (pintype "passive"))
      (node (ref "R36") (pin "2") (pinfunction "2_2") (pintype "passive"))
      (node (ref "R40") (pin "1") (pinfunction "1_1") (pintype "passive"))
    )
    (net (code "57") (name "Net-(IC7-IN-)") (class "Default")
      (node (ref "IC7") (pin "4") (pinfunction "IN-_4") (pintype "passive"))
      (node (ref "R47") (pin "2") (pinfunction "2_2") (pintype "passive"))
    )
    (net (code "58") (name "Net-(IC8-IN+)") (class "Default")
      (node (ref "IC8") (pin "3") (pinfunction "IN+_3") (pintype "passive"))
      (node (ref "R50") (pin "1") (pinfunction "1_1") (pintype "passive"))
    )
    (net (code "59") (name "Net-(IC8-IN-)") (class "Default")
      (node (ref "IC8") (pin "4") (pinfunction "IN-_4") (pintype "passive"))
      (node (ref "R49") (pin "1") (pinfunction "1_1") (pintype "passive"))
      (node (ref "R51") (pin "2") (pinfunction "2_2") (pintype "passive"))
    )
    (net (code "60") (name "Net-(IC8-OUT)") (class "Default")
      (node (ref "IC8") (pin "1") (pinfunction "OUT_1") (pintype "passive"))
      (node (ref "R51") (pin "1") (pinfunction "1_1") (pintype "passive"))
      (node (ref "R52") (pin "2") (pinfunction "2_2") (pintype "passive"))
    )
    (net (code "61") (name "Net-(IC10-D)") (class "Default")
      (node (ref "IC10") (pin "4") (pinfunction "D_4") (pintype "bidirectional"))
      (node (ref "R98") (pin "1") (pinfunction "1_1") (pintype "passive"))
    )
    (net (code "62") (name "Net-(IC10-DE)") (class "Default")
      (node (ref "IC10") (pin "3") (pinfunction "DE_3") (pintype "bidirectional"))
      (node (ref "R96") (pin "2") (pinfunction "2_2") (pintype "passive"))
      (node (ref "R97") (pin "1") (pinfunction "1_1") (pintype "passive"))
    )
    (net (code "63") (name "Net-(IC10-R)") (class "Default")
      (node (ref "IC10") (pin "1") (pinfunction "R_1") (pintype "bidirectional"))
      (node (ref "R93") (pin "2") (pinfunction "2_2") (pintype "passive"))
    )
    (net (code "64") (name "Net-(IC10-{slash}RE)") (class "Default")
      (node (ref "IC10") (pin "2") (pinfunction "/RE_2") (pintype "bidirectional"))
      (node (ref "R96") (pin "1") (pinfunction "1_1") (pintype "passive"))
    )
    (net (code "65") (name "Net-(IC11-BST)") (class "Default")
      (node (ref "C38") (pin "1") (pinfunction "1_1") (pintype "passive"))
      (node (ref "IC11") (pin "6") (pinfunction "BST_6") (pintype "bidirectional"))
    )
    (net (code "66") (name "Net-(IC11-EN)") (class "Default")
      (node (ref "IC11") (pin "5") (pinfunction "EN_5") (pintype "bidirectional"))
      (node (ref "R81") (pin "2") (pinfunction "2_2") (pintype "passive"))
      (node (ref "R82") (pin "1") (pinfunction "1_1") (pintype "passive"))
    )
    (net (code "67") (name "Net-(IC11-FB)") (class "Default")
      (node (ref "IC11") (pin "4") (pinfunction "FB_4") (pintype "bidirectional"))
      (node (ref "R101") (pin "1") (pinfunction "1_1") (pintype "passive"))
      (node (ref "R102") (pin "2") (pinfunction "2_2") (pintype "passive"))
    )
    (net (code "68") (name "Net-(IC11-SW)") (class "Default")
      (node (ref "C38") (pin "2") (pinfunction "2_2") (pintype "passive"))
      (node (ref "IC11") (pin "2") (pinfunction "SW_2") (pintype "bidirectional"))
      (node (ref "L2") (pin "1") (pinfunction "P$1_1") (pintype "bidirectional"))
    )
    (net (code "69") (name "Net-(IC15-IN+)") (class "Default")
      (node (ref "C52") (pin "2") (pinfunction "2_2") (pintype "passive"))
      (node (ref "IC15") (pin "3") (pinfunction "IN+_3") (pintype "passive"))
      (node (ref "R106") (pin "1") (pinfunction "1_1") (pintype "passive"))
      (node (ref "R107") (pin "1") (pinfunction "1_1") (pintype "passive"))
    )
    (net (code "70") (name "Net-(IC15-IN-)") (class "Default")
      (node (ref "IC15") (pin "4") (pinfunction "IN-_4") (pintype "passive"))
      (node (ref "R105") (pin "2") (pinfunction "2_2") (pintype "passive"))
    )
    (net (code "71") (name "Net-(IC15-OUT)") (class "Default")
      (node (ref "IC15") (pin "1") (pinfunction "OUT_1") (pintype "passive"))
      (node (ref "R105") (pin "1") (pinfunction "1_1") (pintype "passive"))
      (node (ref "R50") (pin "2") (pinfunction "2_2") (pintype "passive"))
    )
    (net (code "72") (name "Net-(J1-ID)") (class "Default")
      (node (ref "J1") (pin "4") (pinfunction "ID_4") (pintype "bidirectional"))
      (node (ref "R1") (pin "1") (pinfunction "1_1") (pintype "passive"))
    )
    (net (code "73") (name "Net-(J4-Pad02)") (class "Default")
      (node (ref "J4") (pin "02") (pinfunction "02_02") (pintype "passive"))
      (node (ref "R20") (pin "2") (pinfunction "2_2") (pintype "passive"))
    )
    (net (code "74") (name "Net-(J4-Pad03)") (class "Default")
      (node (ref "J4") (pin "03") (pinfunction "03_03") (pintype "passive"))
      (node (ref "R21") (pin "2") (pinfunction "2_2") (pintype "passive"))
    )
    (net (code "75") (name "Net-(Q1-B)") (class "Default")
      (node (ref "Q1") (pin "1") (pinfunction "B_1") (pintype "passive"))
      (node (ref "R3") (pin "1") (pinfunction "1_1") (pintype "passive"))
      (node (ref "R4") (pin "1") (pinfunction "1_1") (pintype "passive"))
    )
    (net (code "76") (name "Net-(Q3-D)") (class "Default")
      (node (ref "Q3") (pin "3") (pinfunction "D_3") (pintype "passive"))
      (node (ref "R27") (pin "1") (pinfunction "1_1") (pintype "passive"))
    )
    (net (code "77") (name "Net-(Q3-G)") (class "Default")
      (node (ref "Q3") (pin "1") (pinfunction "G_1") (pintype "passive"))
      (node (ref "R28") (pin "2") (pinfunction "2_2") (pintype "passive"))
      (node (ref "R29") (pin "1") (pinfunction "1_1") (pintype "passive"))
    )
    (net (code "78") (name "Net-(Q5-D)") (class "Default")
      (node (ref "Q5") (pin "3") (pinfunction "D_3") (pintype "passive"))
      (node (ref "R75") (pin "1") (pinfunction "1_1") (pintype "passive"))
    )
    (net (code "79") (name "Net-(Q5-G)") (class "Default")
      (node (ref "Q5") (pin "1") (pinfunction "G_1") (pintype "passive"))
      (node (ref "R71") (pin "2") (pinfunction "2_2") (pintype "passive"))
      (node (ref "R74") (pin "1") (pinfunction "1_1") (pintype "passive"))
    )
    (net (code "80") (name "Net-(Q7-D)") (class "Default")
      (node (ref "Q7") (pin "3") (pinfunction "D_3") (pintype "passive"))
      (node (ref "R76") (pin "1") (pinfunction "1_1") (pintype "passive"))
    )
    (net (code "81") (name "Net-(Q7-G)") (class "Default")
      (node (ref "Q7") (pin "1") (pinfunction "G_1") (pintype "passive"))
      (node (ref "R77") (pin "1") (pinfunction "1_1") (pintype "passive"))
      (node (ref "R78") (pin "2") (pinfunction "2_2") (pintype "passive"))
    )
    (net (code "82") (name "Net-(Q9-D)") (class "Default")
      (node (ref "Q9") (pin "3") (pinfunction "D_3") (pintype "passive"))
      (node (ref "R87") (pin "1") (pinfunction "1_1") (pintype "passive"))
    )
    (net (code "83") (name "Net-(Q9-G)") (class "Default")
      (node (ref "Q9") (pin "1") (pinfunction "G_1") (pintype "passive"))
      (node (ref "R85") (pin "1") (pinfunction "1_1") (pintype "passive"))
      (node (ref "R88") (pin "2") (pinfunction "2_2") (pintype "passive"))
    )
    (net (code "84") (name "Net-(R16-Pad1)") (class "Default")
      (node (ref "R16") (pin "1") (pinfunction "1_1") (pintype "passive"))
      (node (ref "X3") (pin "6") (pinfunction "6_6") (pintype "bidirectional"))
    )
    (net (code "85") (name "Net-(R17-Pad1)") (class "Default")
      (node (ref "R17") (pin "1") (pinfunction "1_1") (pintype "passive"))
      (node (ref "X3") (pin "8") (pinfunction "8_8") (pintype "bidirectional"))
    )
    (net (code "86") (name "Net-(R18-Pad1)") (class "Default")
      (node (ref "R18") (pin "1") (pinfunction "1_1") (pintype "passive"))
      (node (ref "X3") (pin "10") (pinfunction "10_10") (pintype "bidirectional"))
    )
    (net (code "87") (name "Net-(R22-Pad2)") (class "Default")
      (node (ref "R22") (pin "2") (pinfunction "2_2") (pintype "passive"))
      (node (ref "R25") (pin "1") (pinfunction "1_1") (pintype "passive"))
      (node (ref "V4") (pin "1") (pinfunction "1_1") (pintype "passive"))
      (node (ref "X6") (pin "1") (pinfunction "1_1") (pintype "bidirectional"))
    )
    (net (code "88") (name "Net-(R61-Pad2)") (class "Default")
      (node (ref "R61") (pin "2") (pinfunction "2_2") (pintype "passive"))
      (node (ref "X8") (pin "6") (pinfunction "6_6") (pintype "passive"))
    )
    (net (code "89") (name "Net-(R62-Pad2)") (class "Default")
      (node (ref "R62") (pin "2") (pinfunction "2_2") (pintype "passive"))
      (node (ref "X8") (pin "1") (pinfunction "1_1") (pintype "passive"))
    )
    (net (code "90") (name "Net-(R63-Pad2)") (class "Default")
      (node (ref "R63") (pin "2") (pinfunction "2_2") (pintype "passive"))
      (node (ref "X8") (pin "2") (pinfunction "2_2") (pintype "passive"))
    )
    (net (code "91") (name "Net-(R65-Pad1)") (class "Default")
      (node (ref "R65") (pin "1") (pinfunction "1_1") (pintype "passive"))
      (node (ref "X8") (pin "5") (pinfunction "5_5") (pintype "passive"))
    )
    (net (code "92") (name "Net-(R66-Pad2)") (class "Default")
      (node (ref "R66") (pin "2") (pinfunction "2_2") (pintype "passive"))
      (node (ref "X9") (pin "6") (pinfunction "6_6") (pintype "passive"))
    )
    (net (code "93") (name "Net-(R67-Pad2)") (class "Default")
      (node (ref "R67") (pin "2") (pinfunction "2_2") (pintype "passive"))
      (node (ref "X9") (pin "1") (pinfunction "1_1") (pintype "passive"))
    )
    (net (code "94") (name "Net-(R68-Pad2)") (class "Default")
      (node (ref "R68") (pin "2") (pinfunction "2_2") (pintype "passive"))
      (node (ref "X9") (pin "2") (pinfunction "2_2") (pintype "passive"))
    )
    (net (code "95") (name "Net-(R70-Pad1)") (class "Default")
      (node (ref "R70") (pin "1") (pinfunction "1_1") (pintype "passive"))
      (node (ref "X9") (pin "5") (pinfunction "5_5") (pintype "passive"))
    )
    (net (code "96") (name "Net-(R80-Pad1)") (class "Default")
      (node (ref "R80") (pin "1") (pinfunction "1_1") (pintype "passive"))
      (node (ref "R84") (pin "2") (pinfunction "2_2") (pintype "passive"))
      (node (ref "V8") (pin "1") (pinfunction "1_1") (pintype "passive"))
      (node (ref "X4") (pin "1") (pinfunction "1_1") (pintype "bidirectional"))
    )
    (net (code "97") (name "Net-(R93-Pad1)") (class "Default")
      (node (ref "R93") (pin "1") (pinfunction "1_1") (pintype "passive"))
      (node (ref "R94") (pin "2") (pinfunction "2_2") (pintype "passive"))
      (node (ref "R95") (pin "1") (pinfunction "1_1") (pintype "passive"))
    )
    (net (code "98") (name "O2_SENSOR1_C") (class "Default")
      (node (ref "C11") (pin "1") (pinfunction "1_1") (pintype "passive"))
      (node (ref "IC4") (pin "1") (pinfunction "OUT_1") (pintype "passive"))
      (node (ref "X17") (pin "2") (pinfunction "2_2") (pintype "bidirectional"))
    )
    (net (code "99") (name "O2_SENSOR1_R") (class "Default")
      (node (ref "R34") (pin "1") (pinfunction "1_1") (pintype "passive"))
      (node (ref "X17") (pin "1") (pinfunction "1_1") (pintype "bidirectional"))
    )
    (net (code "100") (name "O2_SENSOR1_S") (class "Default")
      (node (ref "R35") (pin "2") (pinfunction "2_2") (pintype "passive"))
      (node (ref "X17") (pin "3") (pinfunction "3_3") (pintype "bidirectional"))
    )
    (net (code "101") (name "O2_SENSOR2_C") (class "Default")
      (node (ref "C17") (pin "1") (pinfunction "1_1") (pintype "passive"))
      (node (ref "IC7") (pin "1") (pinfunction "OUT_1") (pintype "passive"))
      (node (ref "X18") (pin "2") (pinfunction "2_2") (pintype "bidirectional"))
    )
    (net (code "102") (name "O2_SENSOR2_R") (class "Default")
      (node (ref "R48") (pin "1") (pinfunction "1_1") (pintype "passive"))
      (node (ref "X18") (pin "1") (pinfunction "1_1") (pintype "bidirectional"))
    )
    (net (code "103") (name "O2_SENSOR2_S") (class "Default")
      (node (ref "R49") (pin "2") (pinfunction "2_2") (pintype "passive"))
      (node (ref "X18") (pin "3") (pinfunction "3_3") (pintype "bidirectional"))
    )
    (net (code "104") (name "RS485-A") (class "Default")
      (node (ref "IC10") (pin "6") (pinfunction "A_6") (pintype "bidirectional"))
      (node (ref "J3") (pin "1") (pinfunction "1_1") (pintype "passive"))
      (node (ref "R100") (pin "2") (pinfunction "2_2") (pintype "passive"))
      (node (ref "V9") (pin "2") (pinfunction "2_2") (pintype "passive"))
    )
    (net (code "105") (name "RS485-B") (class "Default")
      (node (ref "IC10") (pin "7") (pinfunction "B_7") (pintype "bidirectional"))
      (node (ref "J3") (pin "2") (pinfunction "2_2") (pintype "passive"))
      (node (ref "R99") (pin "2") (pinfunction "2_2") (pintype "passive"))
      (node (ref "V10") (pin "2") (pinfunction "2_2") (pintype "passive"))
    )
    (net (code "106") (name "TEMP_SENSOR_A") (class "Default")
      (node (ref "R92") (pin "2") (pinfunction "2_2") (pintype "passive"))
      (node (ref "X24") (pin "1") (pinfunction "1_1") (pintype "bidirectional"))
    )
    (net (code "107") (name "TEMP_SENSOR_C") (class "Default")
      (node (ref "R90") (pin "1") (pinfunction "1_1") (pintype "passive"))
      (node (ref "R91") (pin "1") (pinfunction "1_1") (pintype "passive"))
      (node (ref "X24") (pin "3") (pinfunction "3_3") (pintype "bidirectional"))
    )
    (net (code "108") (name "USB_DM") (class "Default")
      (node (ref "IC1") (pin "43") (pinfunction "PA11_[PA9]_43") (pintype "bidirectional"))
      (node (ref "J1") (pin "2") (pinfunction "D-_2") (pintype "bidirectional"))
      (node (ref "V2") (pin "2") (pinfunction "2_2") (pintype "passive"))
    )
    (net (code "109") (name "USB_DP") (class "Default")
      (node (ref "IC1") (pin "44") (pinfunction "PA12_[PA10]_44") (pintype "bidirectional"))
      (node (ref "J1") (pin "3") (pinfunction "D+_3") (pintype "bidirectional"))
      (node (ref "V1") (pin "2") (pinfunction "2_2") (pintype "passive"))
    )
    (net (code "110") (name "V3V3") (class "Default")
      (node (ref "C3") (pin "1") (pinfunction "1_1") (pintype "passive"))
      (node (ref "C30") (pin "1") (pinfunction "1_1") (pintype "passive"))
      (node (ref "C34") (pin "1") (pinfunction "+_1") (pintype "passive"))
      (node (ref "C37") (pin "1") (pinfunction "1_1") (pintype "passive"))
      (node (ref "C4") (pin "2") (pinfunction "2_2") (pintype "passive"))
      (node (ref "C45") (pin "1") (pinfunction "1_1") (pintype "passive"))
      (node (ref "C46") (pin "1") (pinfunction "1_1") (pintype "passive"))
      (node (ref "C6") (pin "1") (pinfunction "1_1") (pintype "passive"))
      (node (ref "C7") (pin "1") (pinfunction "1_1") (pintype "passive"))
      (node (ref "C8") (pin "1") (pinfunction "1_1") (pintype "passive"))
      (node (ref "C9") (pin "1") (pinfunction "1_1") (pintype "passive"))
      (node (ref "IC1") (pin "7") (pinfunction "VREF+_7") (pintype "bidirectional"))
      (node (ref "IC1") (pin "8") (pinfunction "VDD/VDDA_8") (pintype "bidirectional"))
      (node (ref "IC13") (pin "4") (pinfunction "OUT_4") (pintype "passive"))
      (node (ref "IC3") (pin "5") (pinfunction "NULL_5") (pintype "passive"))
      (node (ref "J4") (pin "01") (pinfunction "01_01") (pintype "passive"))
      (node (ref "R10") (pin "2") (pinfunction "2_2") (pintype "passive"))
      (node (ref "R19") (pin "2") (pinfunction "2_2") (pintype "passive"))
      (node (ref "R23") (pin "2") (pinfunction "2_2") (pintype "passive"))
      (node (ref "R24") (pin "2") (pinfunction "2_2") (pintype "passive"))
      (node (ref "R25") (pin "2") (pinfunction "2_2") (pintype "passive"))
      (node (ref "R59") (pin "2") (pinfunction "2_2") (pintype "passive"))
      (node (ref "R60") (pin "2") (pinfunction "2_2") (pintype "passive"))
      (node (ref "R80") (pin "2") (pinfunction "2_2") (pintype "passive"))
      (node (ref "R90") (pin "2") (pinfunction "2_2") (pintype "passive"))
      (node (ref "X3") (pin "2") (pinfunction "2_2") (pintype "bidirectional"))
    )
    (net (code "111") (name "V5V0") (class "Default")
      (node (ref "C10") (pin "1") (pinfunction "1_1") (pintype "passive"))
      (node (ref "C12") (pin "1") (pinfunction "1_1") (pintype "passive"))
      (node (ref "C14") (pin "2") (pinfunction "2_2") (pintype "passive"))
      (node (ref "C16") (pin "1") (pinfunction "1_1") (pintype "passive"))
      (node (ref "C18") (pin "1") (pinfunction "1_1") (pintype "passive"))
      (node (ref "C24") (pin "2") (pinfunction "2_2") (pintype "passive"))
      (node (ref "C25") (pin "2") (pinfunction "2_2") (pintype "passive"))
      (node (ref "C29") (pin "1") (pinfunction "1_1") (pintype "passive"))
      (node (ref "C33") (pin "1") (pinfunction "+_1") (pintype "passive"))
      (node (ref "C36") (pin "1") (pinfunction "1_1") (pintype "passive"))
      (node (ref "C43") (pin "1") (pinfunction "1_1") (pintype "passive"))
      (node (ref "C44") (pin "1") (pinfunction "1_1") (pintype "passive"))
      (node (ref "C50") (pin "1") (pinfunction "1_1") (pintype "passive"))
      (node (ref "IC10") (pin "8") (pinfunction "VCC_8") (pintype "bidirectional"))
      (node (ref "IC12") (pin "4") (pinfunction "OUT_4") (pintype "passive"))
      (node (ref "IC13") (pin "3") (pinfunction "IN_3") (pintype "input"))
      (node (ref "IC15") (pin "5") (pinfunction "VCC_5") (pintype "passive"))
      (node (ref "IC4") (pin "5") (pinfunction "VCC_5") (pintype "passive"))
      (node (ref "IC5") (pin "5") (pinfunction "VCC_5") (pintype "passive"))
      (node (ref "IC6") (pin "5") (pinfunction "VCC_5") (pintype "passive"))
      (node (ref "IC7") (pin "5") (pinfunction "VCC_5") (pintype "passive"))
      (node (ref "IC8") (pin "5") (pinfunction "VCC_5") (pintype "passive"))
      (node (ref "J2") (pin "04") (pinfunction "04_04") (pintype "passive"))
      (node (ref "R107") (pin "2") (pinfunction "2_2") (pintype "passive"))
      (node (ref "R32") (pin "2") (pinfunction "2_2") (pintype "passive"))
      (node (ref "R42") (pin "2") (pinfunction "2_2") (pintype "passive"))
      (node (ref "R46") (pin "2") (pinfunction "2_2") (pintype "passive"))
      (node (ref "R6") (pin "1") (pinfunction "1_1") (pintype "passive"))
      (node (ref "R64") (pin "1") (pinfunction "1_1") (pintype "passive"))
      (node (ref "R69") (pin "1") (pinfunction "1_1") (pintype "passive"))
      (node (ref "R9") (pin "2") (pinfunction "2_2") (pintype "passive"))
      (node (ref "X8") (pin "3") (pinfunction "3_3") (pintype "passive"))
      (node (ref "X9") (pin "3") (pinfunction "3_3") (pintype "passive"))
    )
    (net (code "112") (name "V24V0") (class "Default")
      (node (ref "C28") (pin "1") (pinfunction "1_1") (pintype "passive"))
      (node (ref "C39") (pin "1") (pinfunction "1_1") (pintype "passive"))
      (node (ref "F1") (pin "2") (pinfunction "P$2_2") (pintype "bidirectional"))
      (node (ref "IC11") (pin "3") (pinfunction "VIN_3") (pintype "bidirectional"))
      (node (ref "K1") (pin "11") (pinfunction "4_11") (pintype "passive"))
      (node (ref "K2") (pin "11") (pinfunction "4_11") (pintype "passive"))
      (node (ref "R81") (pin "1") (pinfunction "1_1") (pintype "passive"))
      (node (ref "V5") (pin "1") (pinfunction "1_1") (pintype "passive"))
      (node (ref "V6") (pin "1") (pinfunction "1_1") (pintype "passive"))
    )
    (net (code "113") (name "V24V0_B4_FUSE") (class "Default")
      (node (ref "C27") (pin "1") (pinfunction "1_1") (pintype "passive"))
      (node (ref "C41") (pin "1") (pinfunction "+_1") (pintype "passive"))
      (node (ref "F1") (pin "1") (pinfunction "P$1_1") (pintype "bidirectional"))
      (node (ref "X15") (pin "1") (pinfunction "1_1") (pintype "passive"))
      (node (ref "X15") (pin "1-2") (pinfunction "1_1-2") (pintype "passive"))
    )
    (net (code "114") (name "VBUS") (class "Default")
      (node (ref "J1") (pin "1") (pinfunction "VBUS_1") (pintype "power_in"))
    )
    (net (code "115") (name "VREF_O2_1") (class "Default")
      (node (ref "C51") (pin "2") (pinfunction "2_2") (pintype "passive"))
      (node (ref "IC7") (pin "3") (pinfunction "IN+_3") (pintype "passive"))
      (node (ref "R45") (pin "2") (pinfunction "2_2") (pintype "passive"))
      (node (ref "R46") (pin "1") (pinfunction "1_1") (pintype "passive"))
    )
    (net (code "116") (name "VREF_O2_2") (class "Default")
      (node (ref "IC4") (pin "3") (pinfunction "IN+_3") (pintype "passive"))
      (node (ref "R31") (pin "2") (pinfunction "2_2") (pintype "passive"))
      (node (ref "R32") (pin "1") (pinfunction "1_1") (pintype "passive"))
    )
    (net (code "117") (name "V_12V0") (class "Default")
      (node (ref "C26") (pin "1") (pinfunction "1_1") (pintype "passive"))
      (node (ref "C31") (pin "1") (pinfunction "1_1") (pintype "passive"))
      (node (ref "C32") (pin "1") (pinfunction "+_1") (pintype "passive"))
      (node (ref "C40") (pin "1") (pinfunction "1_1") (pintype "passive"))
      (node (ref "C42") (pin "1") (pinfunction "1_1") (pintype "passive"))
      (node (ref "D14") (pin "3") (pinfunction "C_3") (pintype "passive"))
      (node (ref "D3") (pin "3") (pinfunction "C_3") (pintype "passive"))
      (node (ref "D5") (pin "3") (pinfunction "C_3") (pintype "passive"))
      (node (ref "D7") (pin "3") (pinfunction "C_3") (pintype "passive"))
      (node (ref "IC12") (pin "3") (pinfunction "IN_3") (pintype "input"))
      (node (ref "L2") (pin "2") (pinfunction "P$2_2") (pintype "bidirectional"))
      (node (ref "Q2") (pin "3") (pinfunction "SOURCE_3") (pintype "passive"))
      (node (ref "Q4") (pin "3") (pinfunction "SOURCE_3") (pintype "passive"))
      (node (ref "Q6") (pin "3") (pinfunction "SOURCE_3") (pintype "passive"))
      (node (ref "Q8") (pin "3") (pinfunction "SOURCE_3") (pintype "passive"))
      (node (ref "R101") (pin "2") (pinfunction "2_2") (pintype "passive"))
      (node (ref "R26") (pin "2") (pinfunction "2_2") (pintype "passive"))
      (node (ref "R73") (pin "2") (pinfunction "2_2") (pintype "passive"))
      (node (ref "R83") (pin "2") (pinfunction "2_2") (pintype "passive"))
      (node (ref "R86") (pin "2") (pinfunction "2_2") (pintype "passive"))
    )
    (net (code "118") (name "unconnected-(FID1-PadP$1)") (class "Default")
      (node (ref "FID1") (pin "P$1") (pinfunction "P$1_P$1") (pintype "bidirectional"))
    )
    (net (code "119") (name "unconnected-(FID2-PadP$1)") (class "Default")
      (node (ref "FID2") (pin "P$1") (pinfunction "P$1_P$1") (pintype "bidirectional"))
    )
    (net (code "120") (name "unconnected-(IC1-PA3-Pad20)") (class "Default")
      (node (ref "IC1") (pin "20") (pinfunction "PA3_20") (pintype "bidirectional"))
    )
    (net (code "121") (name "unconnected-(IC1-PA4-Pad21)") (class "Default")
      (node (ref "IC1") (pin "21") (pinfunction "PA4_21") (pintype "bidirectional"))
    )
    (net (code "122") (name "unconnected-(IC1-PA5-Pad22)") (class "Default")
      (node (ref "IC1") (pin "22") (pinfunction "PA5_22") (pintype "bidirectional"))
    )
    (net (code "123") (name "unconnected-(IC1-PA10-Pad42)") (class "Default")
      (node (ref "IC1") (pin "42") (pinfunction "PA10_42") (pintype "bidirectional"))
    )
    (net (code "124") (name "unconnected-(IC1-PB1-Pad28)") (class "Default")
      (node (ref "IC1") (pin "28") (pinfunction "PB1_28") (pintype "bidirectional"))
    )
    (net (code "125") (name "unconnected-(IC1-PB2-Pad29)") (class "Default")
      (node (ref "IC1") (pin "29") (pinfunction "PB2_29") (pintype "bidirectional"))
    )
    (net (code "126") (name "unconnected-(IC1-PB3-Pad57)") (class "Default")
      (node (ref "IC1") (pin "57") (pinfunction "PB3_57") (pintype "bidirectional"))
    )
    (net (code "127") (name "unconnected-(IC1-PB4-Pad58)") (class "Default")
      (node (ref "IC1") (pin "58") (pinfunction "PB4_58") (pintype "bidirectional"))
    )
    (net (code "128") (name "unconnected-(IC1-PB5-Pad59)") (class "Default")
      (node (ref "IC1") (pin "59") (pinfunction "PB5_59") (pintype "bidirectional"))
    )
    (net (code "129") (name "unconnected-(IC1-PB6-Pad60)") (class "Default")
      (node (ref "IC1") (pin "60") (pinfunction "PB6_60") (pintype "bidirectional"))
    )
    (net (code "130") (name "unconnected-(IC1-PB7-Pad61)") (class "Default")
      (node (ref "IC1") (pin "61") (pinfunction "PB7_61") (pintype "bidirectional"))
    )
    (net (code "131") (name "unconnected-(IC1-PB8-Pad62)") (class "Default")
      (node (ref "IC1") (pin "62") (pinfunction "PB8_62") (pintype "bidirectional"))
    )
    (net (code "132") (name "unconnected-(IC1-PB9-Pad63)") (class "Default")
      (node (ref "IC1") (pin "63") (pinfunction "PB9_63") (pintype "bidirectional"))
    )
    (net (code "133") (name "unconnected-(IC1-PB10-Pad30)") (class "Default")
      (node (ref "IC1") (pin "30") (pinfunction "PB10_30") (pintype "bidirectional"))
    )
    (net (code "134") (name "unconnected-(IC1-PB11-Pad31)") (class "Default")
      (node (ref "IC1") (pin "31") (pinfunction "PB11_31") (pintype "bidirectional"))
    )
    (net (code "135") (name "unconnected-(IC1-PB12-Pad32)") (class "Default")
      (node (ref "IC1") (pin "32") (pinfunction "PB12_32") (pintype "bidirectional"))
    )
    (net (code "136") (name "unconnected-(IC1-PB13-Pad33)") (class "Default")
      (node (ref "IC1") (pin "33") (pinfunction "PB13_33") (pintype "bidirectional"))
    )
    (net (code "137") (name "unconnected-(IC1-PB14-Pad34)") (class "Default")
      (node (ref "IC1") (pin "34") (pinfunction "PB14_34") (pintype "bidirectional"))
    )
    (net (code "138") (name "unconnected-(IC1-PB15-Pad35)") (class "Default")
      (node (ref "IC1") (pin "35") (pinfunction "PB15_35") (pintype "bidirectional"))
    )
    (net (code "139") (name "unconnected-(IC1-PC2-Pad15)") (class "Default")
      (node (ref "IC1") (pin "15") (pinfunction "PC2_15") (pintype "bidirectional"))
    )
    (net (code "140") (name "unconnected-(IC1-PC3-Pad16)") (class "Default")
      (node (ref "IC1") (pin "16") (pinfunction "PC3_16") (pintype "bidirectional"))
    )
    (net (code "141") (name "unconnected-(IC1-PC4-Pad25)") (class "Default")
      (node (ref "IC1") (pin "25") (pinfunction "PC4_25") (pintype "bidirectional"))
    )
    (net (code "142") (name "unconnected-(IC1-PC6-Pad38)") (class "Default")
      (node (ref "IC1") (pin "38") (pinfunction "PC6_38") (pintype "bidirectional"))
    )
    (net (code "143") (name "unconnected-(IC1-PC7-Pad39)") (class "Default")
      (node (ref "IC1") (pin "39") (pinfunction "PC7_39") (pintype "bidirectional"))
    )
    (net (code "144") (name "unconnected-(IC1-PC9-Pad49)") (class "Default")
      (node (ref "IC1") (pin "49") (pinfunction "PC9_49") (pintype "bidirectional"))
    )
    (net (code "145") (name "unconnected-(IC1-PD0-Pad50)") (class "Default")
      (node (ref "IC1") (pin "50") (pinfunction "PD0_50") (pintype "bidirectional"))
    )
    (net (code "146") (name "unconnected-(IC1-PD2-Pad52)") (class "Default")
      (node (ref "IC1") (pin "52") (pinfunction "PD2_52") (pintype "bidirectional"))
    )
    (net (code "147") (name "unconnected-(IC1-PD3-Pad53)") (class "Default")
      (node (ref "IC1") (pin "53") (pinfunction "PD3_53") (pintype "bidirectional"))
    )
    (net (code "148") (name "unconnected-(IC1-PD4-Pad54)") (class "Default")
      (node (ref "IC1") (pin "54") (pinfunction "PD4_54") (pintype "bidirectional"))
    )
    (net (code "149") (name "unconnected-(IC1-PD5-Pad55)") (class "Default")
      (node (ref "IC1") (pin "55") (pinfunction "PD5_55") (pintype "bidirectional"))
    )
    (net (code "150") (name "unconnected-(IC1-PD6-Pad56)") (class "Default")
      (node (ref "IC1") (pin "56") (pinfunction "PD6_56") (pintype "bidirectional"))
    )
    (net (code "151") (name "unconnected-(IC1-PD8-Pad40)") (class "Default")
      (node (ref "IC1") (pin "40") (pinfunction "PD8_40") (pintype "bidirectional"))
    )
    (net (code "152") (name "unconnected-(IC1-PD9-Pad41)") (class "Default")
      (node (ref "IC1") (pin "41") (pinfunction "PD9_41") (pintype "bidirectional"))
    )
    (net (code "153") (name "unconnected-(J3-Pad3)") (class "Default")
      (node (ref "J3") (pin "3") (pinfunction "3_3") (pintype "passive"))
    )
    (net (code "154") (name "unconnected-(J3-Pad4)") (class "Default")
      (node (ref "J3") (pin "4") (pinfunction "4_4") (pintype "passive"))
    )
    (net (code "155") (name "unconnected-(J3-Pad5)") (class "Default")
      (node (ref "J3") (pin "5") (pinfunction "5_5") (pintype "passive"))
    )
    (net (code "156") (name "unconnected-(J3-Pad6)") (class "Default")
      (node (ref "J3") (pin "6") (pinfunction "6_6") (pintype "passive"))
    )
    (net (code "157") (name "unconnected-(J3-Pad7)") (class "Default")
      (node (ref "J3") (pin "7") (pinfunction "7_7") (pintype "passive"))
    )
    (net (code "158") (name "unconnected-(X3-Pad1)") (class "Default")
      (node (ref "X3") (pin "1") (pinfunction "1_1") (pintype "bidirectional"))
    )
    (net (code "159") (name "unconnected-(X3-Pad3)") (class "Default")
      (node (ref "X3") (pin "3") (pinfunction "3_3") (pintype "bidirectional"))
    )
    (net (code "160") (name "unconnected-(X3-Pad5)") (class "Default")
      (node (ref "X3") (pin "5") (pinfunction "5_5") (pintype "bidirectional"))
    )
    (net (code "161") (name "unconnected-(X3-Pad7)") (class "Default")
      (node (ref "X3") (pin "7") (pinfunction "7_7") (pintype "bidirectional"))
    )
    (net (code "162") (name "unconnected-(X3-Pad9)") (class "Default")
      (node (ref "X3") (pin "9") (pinfunction "9_9") (pintype "bidirectional"))
    )
    (net (code "163") (name "unconnected-(X24-Pad2)") (class "Default")
      (node (ref "X24") (pin "2") (pinfunction "2_2") (pintype "bidirectional"))
    )
  )
)
